# MCU.net
KiCad netlist of a schematic drawn in Altium Designer
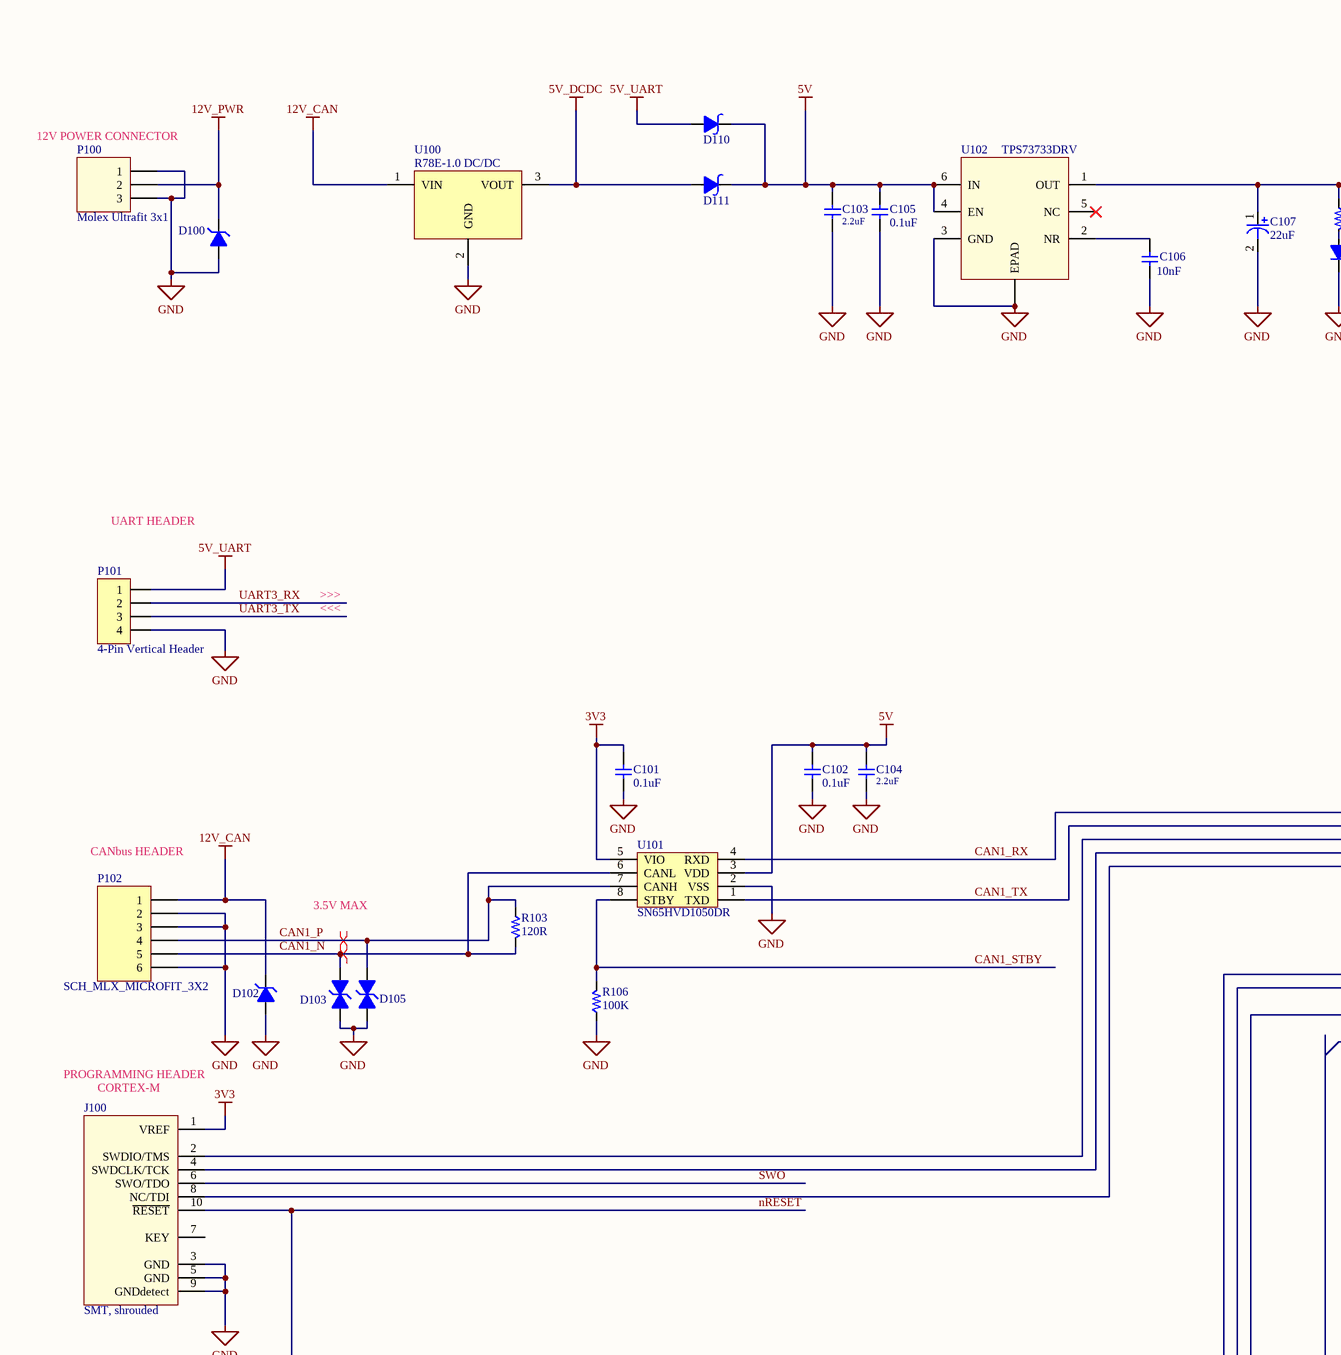
[diagram p0: MCU.SchDoc, top left]
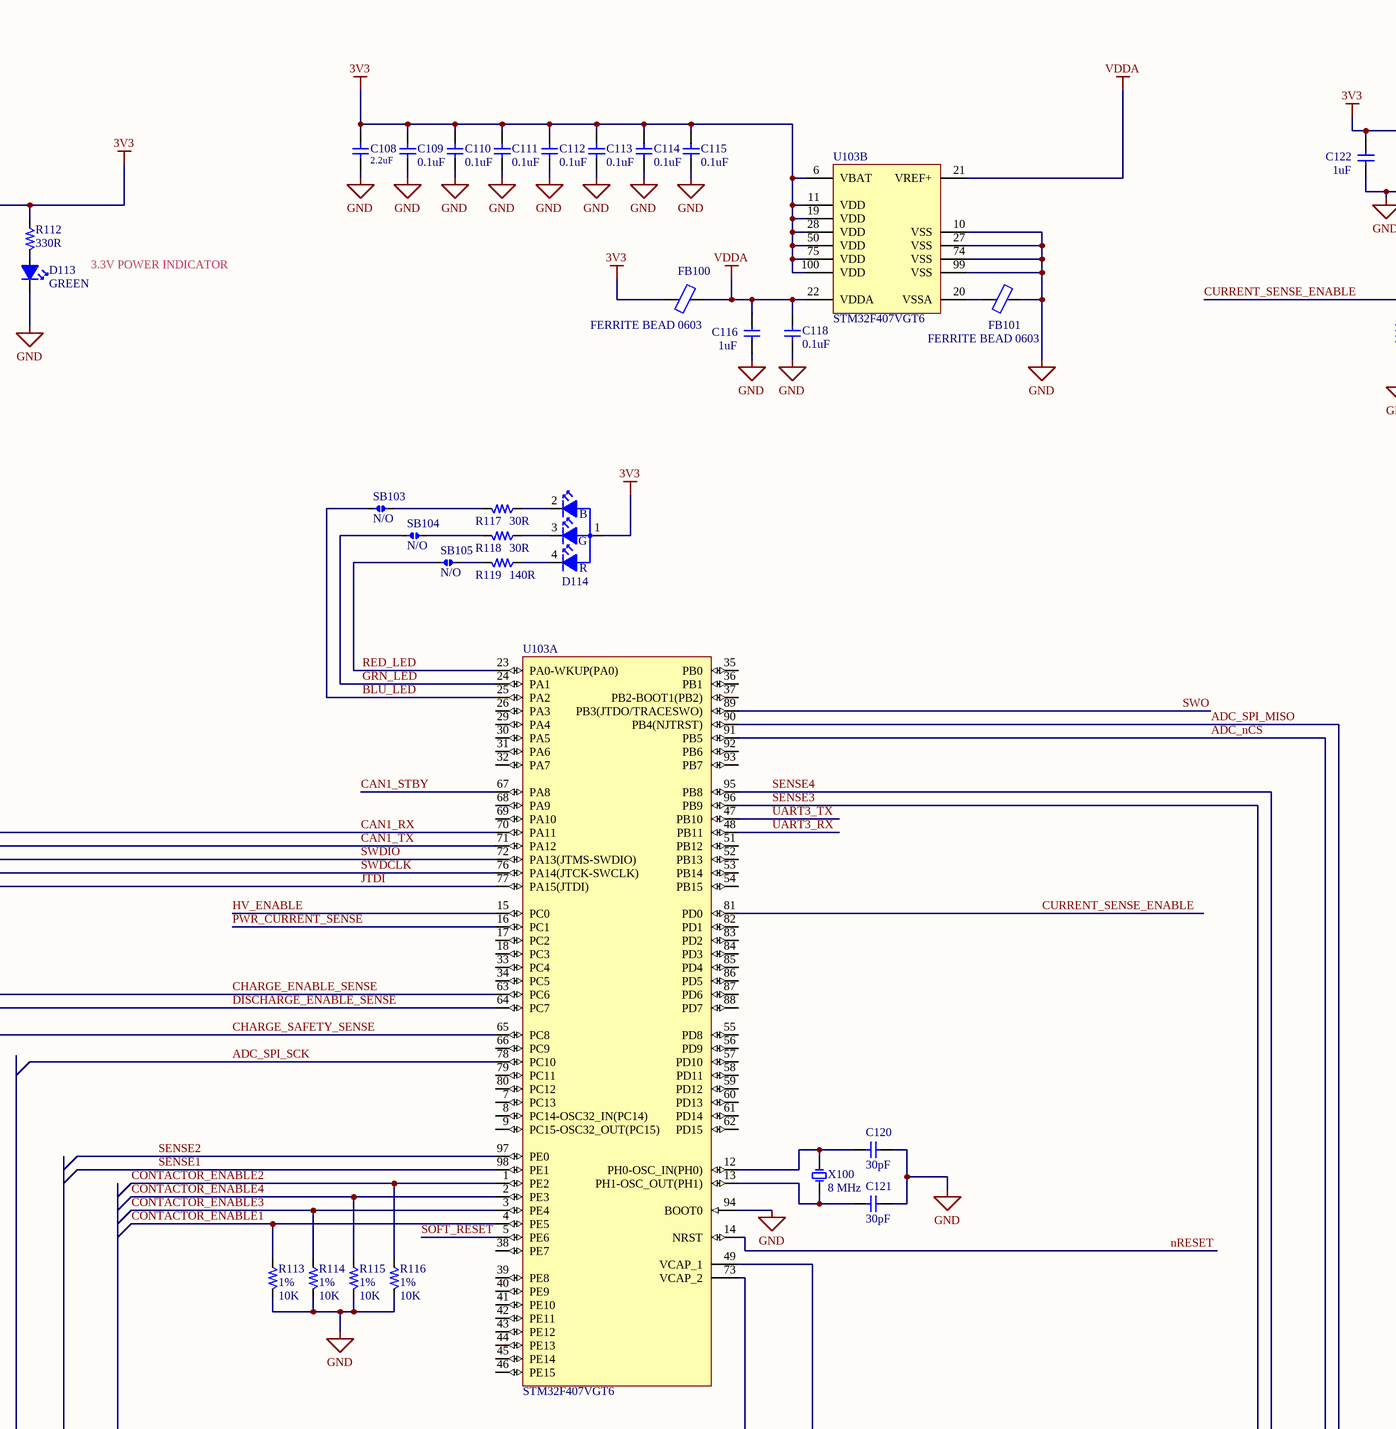
[diagram p1: MCU.SchDoc, top middle]
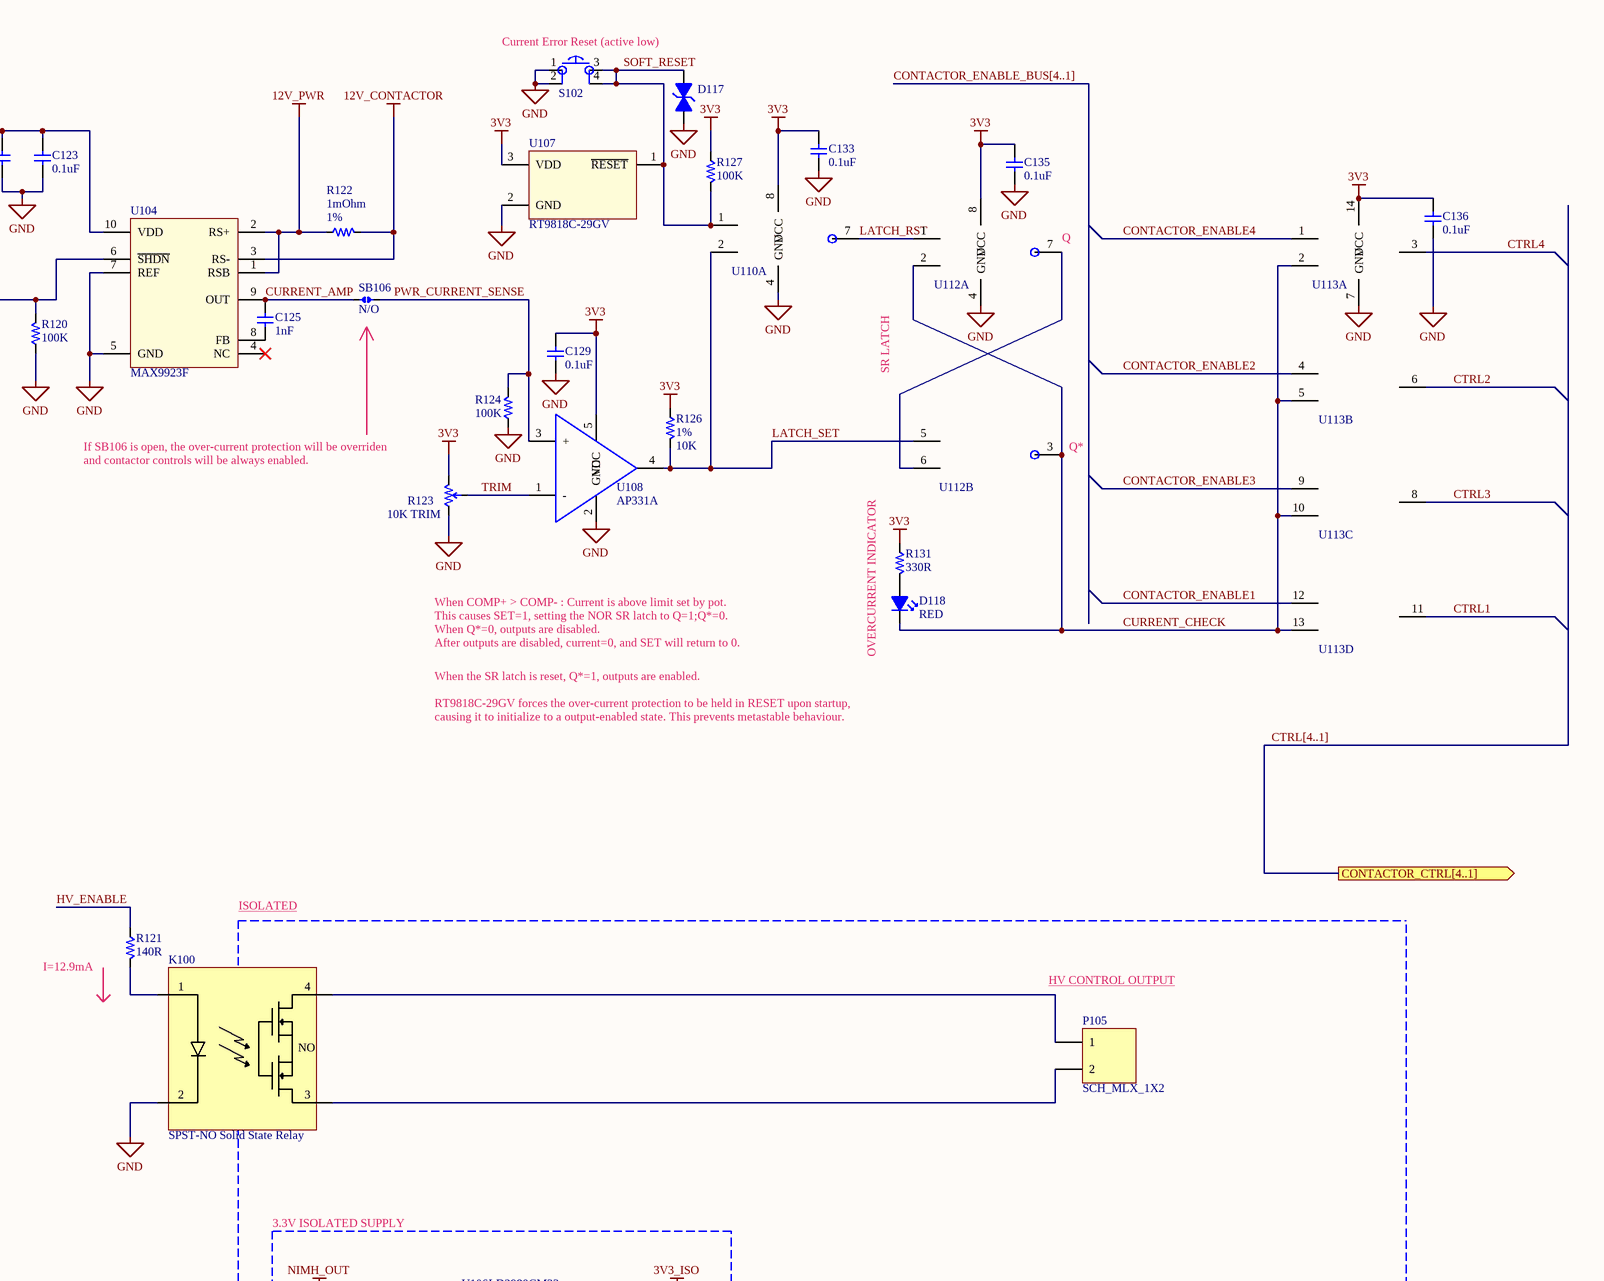
[diagram p2: MCU.SchDoc, top right]
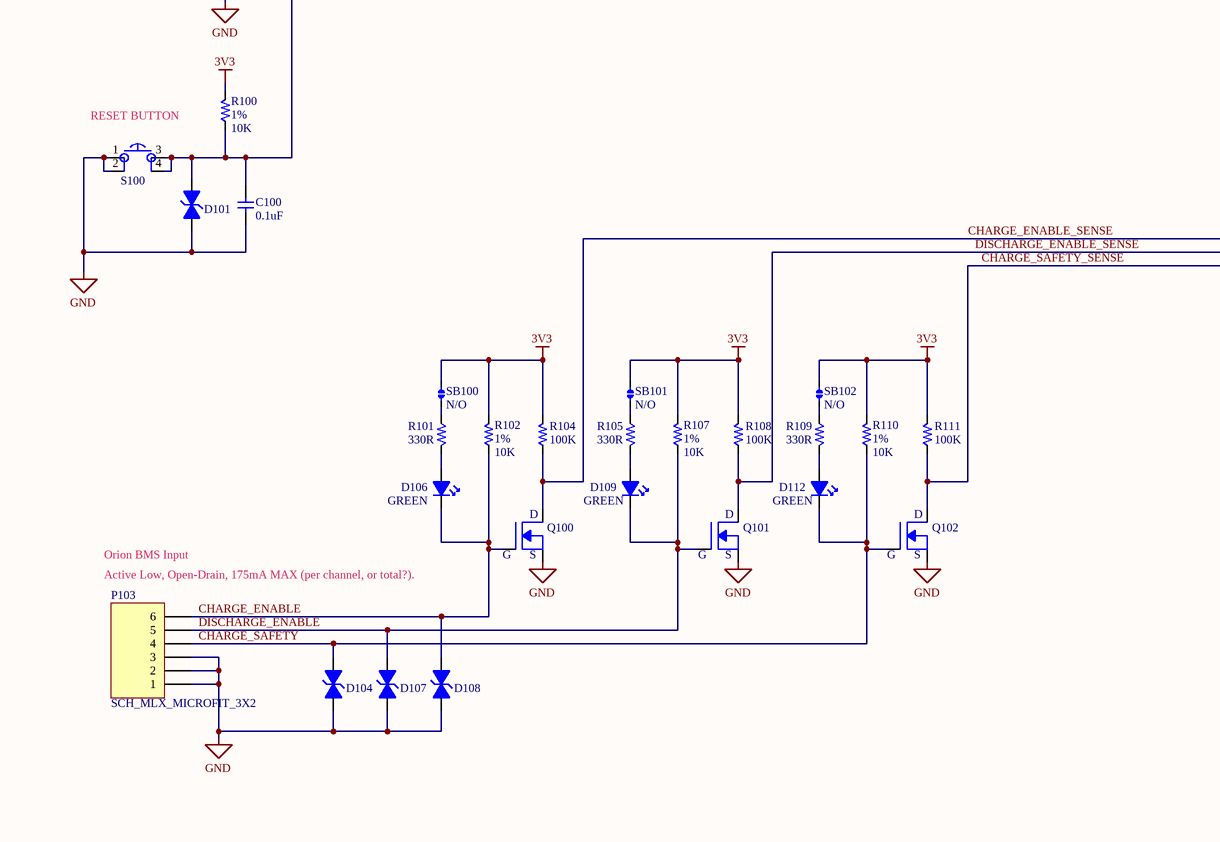
[diagram p3: MCU.SchDoc, bottom left]
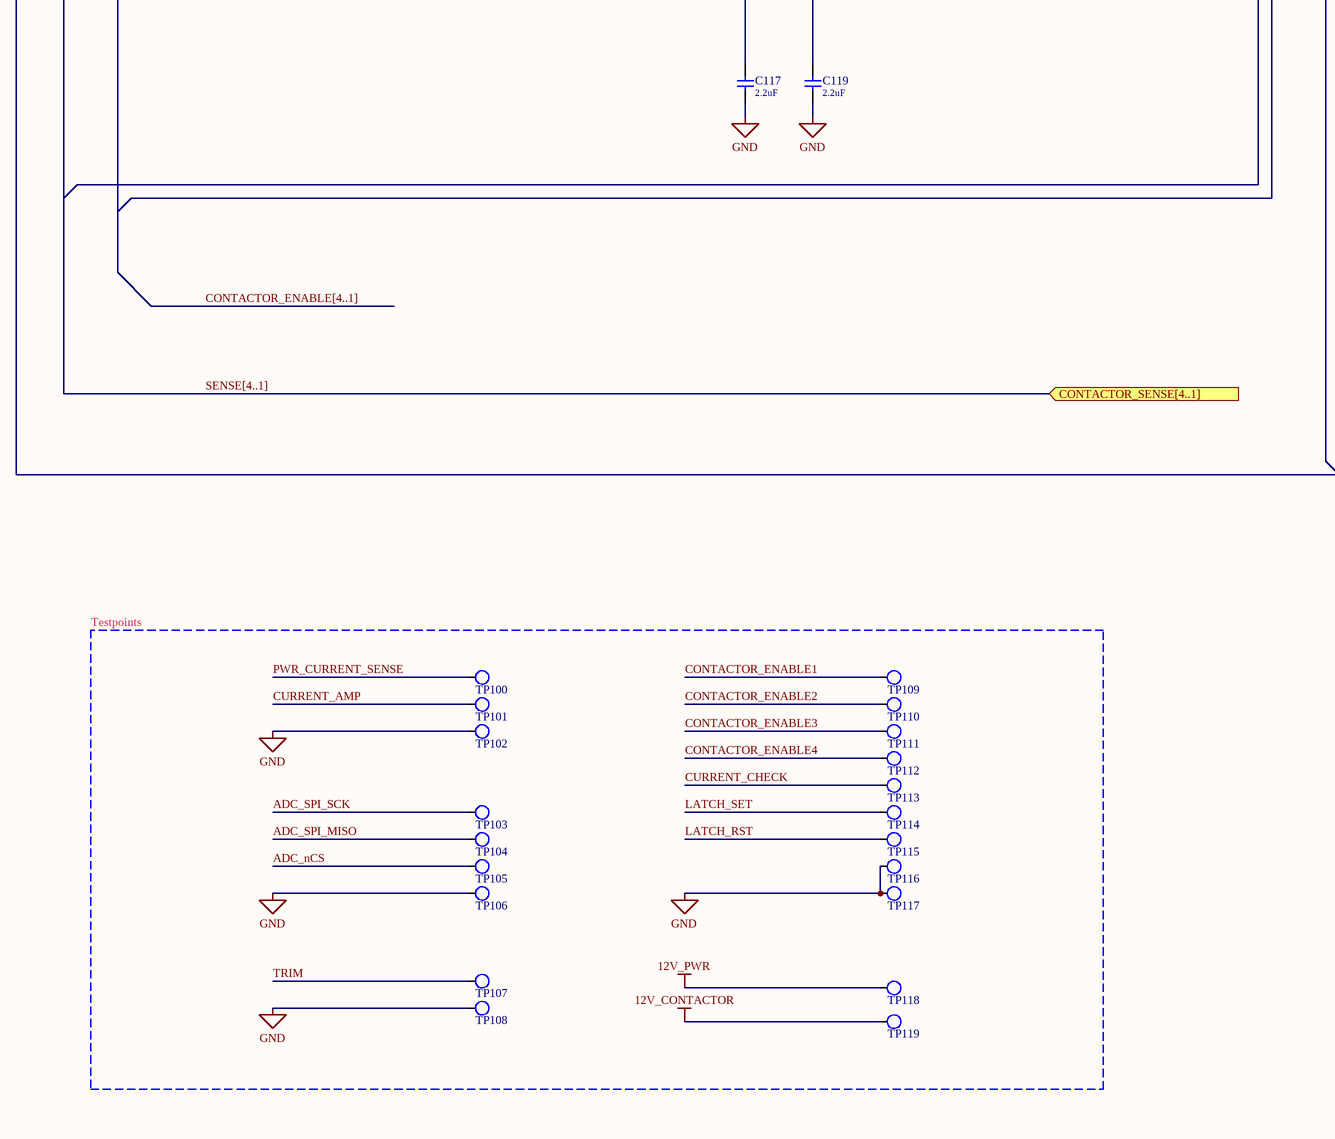
[diagram p4: MCU.SchDoc, bottom middle]
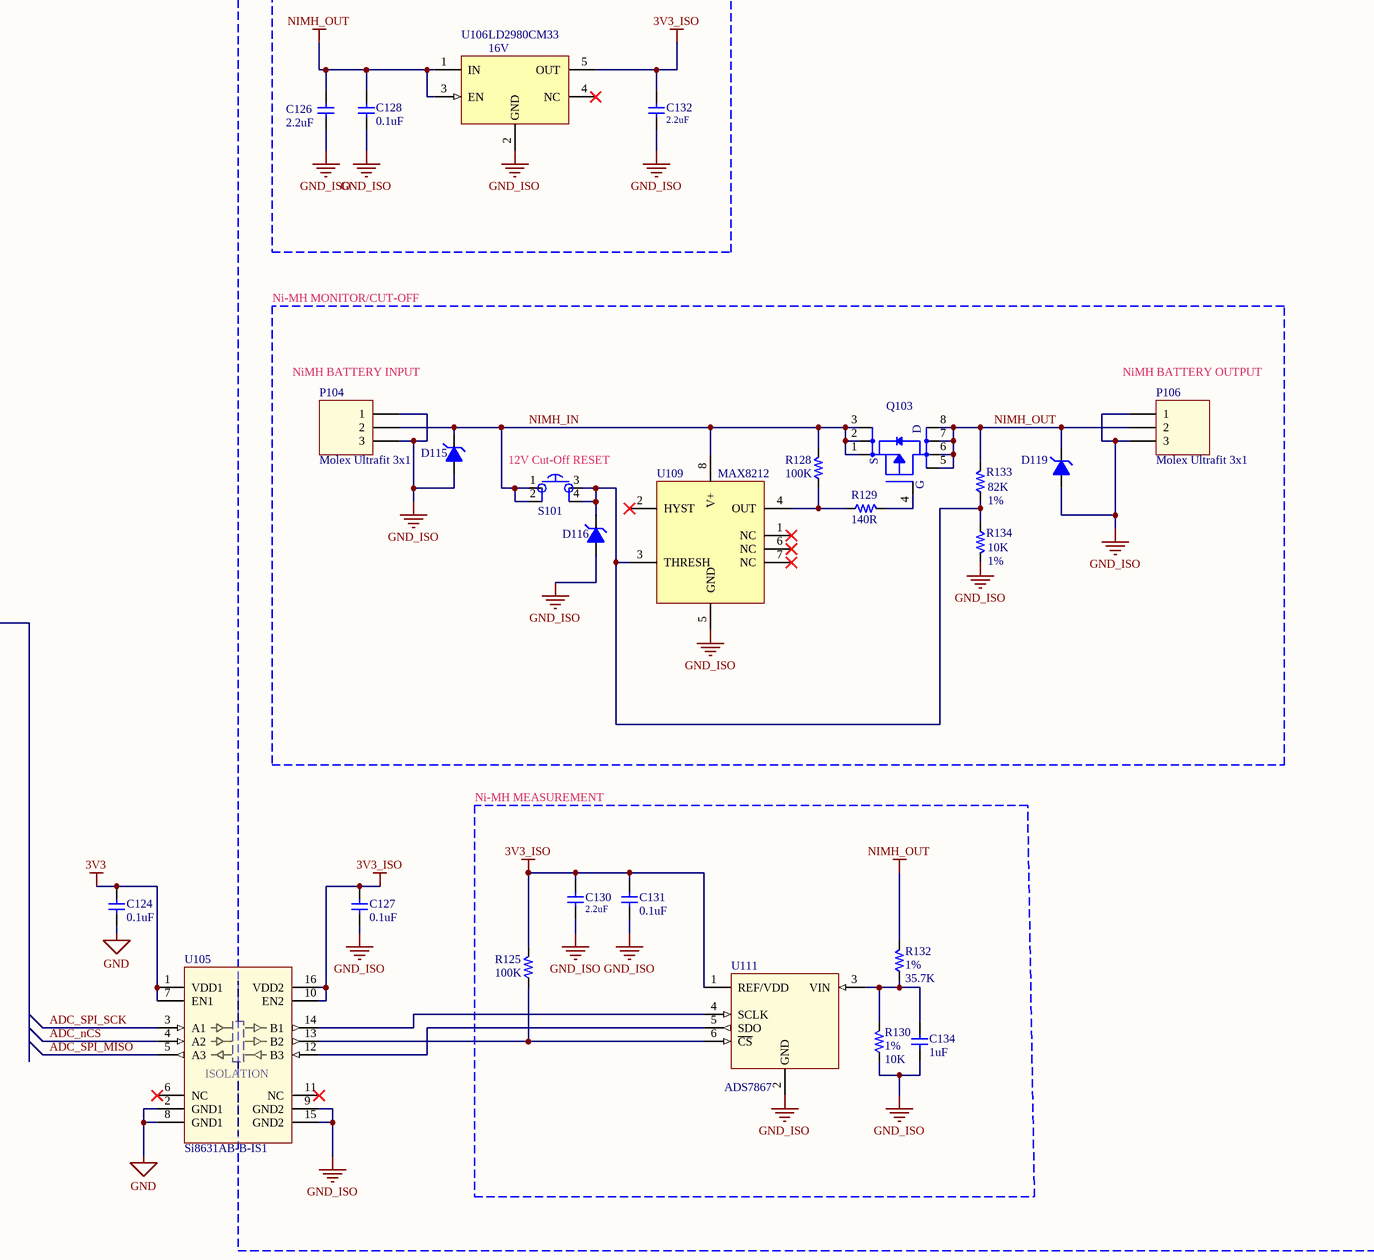
[diagram p5: MCU.SchDoc, bottom right]

(export (version "E")
  (design (tool "Eeschema 10.0.6"))
  (components
    (comp (ref "C100")
      (value "0.1uF")
      (footprint "CAPC1005X06N")
      (description "CAP CER 0402 0.1uF 10V X5R 10%")
      (fields (field (name "TOLERANCE") "10%") (field (name "VOLTAGE") "10V"))
      (libsource (lib "CAP-0402") (part "C040-000U1-00"))
    )
    (comp (ref "C101")
      (value "0.1uF")
      (footprint "CAPC1005X06N")
      (description "CAP CER 0402 0.1uF 10V X5R 10%")
      (fields (field (name "TOLERANCE") "10%") (field (name "VOLTAGE") "10V"))
      (libsource (lib "CAP-0402") (part "C040-000U1-00"))
    )
    (comp (ref "C102")
      (value "0.1uF")
      (footprint "CAPC1005X06N")
      (description "CAP CER 0402 0.1uF 10V X5R 10%")
      (fields (field (name "TOLERANCE") "10%") (field (name "VOLTAGE") "10V"))
      (libsource (lib "CAP-0402") (part "C040-000U1-00"))
    )
    (comp (ref "C103")
      (value "2.2uF")
      (footprint "PCB_GENERIC_SMD_0603")
      (description "CAP CER 0603 2.2uF 16V X5R 20%")
      (fields (field (name "TOLERANCE") "20%") (field (name "VOLTAGE") "16V"))
      (libsource (lib "CAP-0603") (part "C060-002U2-00"))
    )
    (comp (ref "C104")
      (value "2.2uF")
      (footprint "PCB_GENERIC_SMD_0603")
      (description "CAP CER 0603 2.2uF 16V X5R 20%")
      (fields (field (name "TOLERANCE") "20%") (field (name "VOLTAGE") "16V"))
      (libsource (lib "CAP-0603") (part "C060-002U2-00"))
    )
    (comp (ref "C105")
      (value "0.1uF")
      (footprint "CAPC1005X06N")
      (description "CAP CER 0402 0.1uF 10V X5R 10%")
      (fields (field (name "TOLERANCE") "10%") (field (name "VOLTAGE") "10V"))
      (libsource (lib "CAP-0402") (part "C040-000U1-00"))
    )
    (comp (ref "C106")
      (value "10nF")
      (footprint "CAPC1005X06N")
      (description "CAP CER 0402 10nF 50V X7R 10%")
      (fields (field (name "TOLERANCE") "10%") (field (name "VOLTAGE") "50V"))
      (libsource (lib "CAP-0402") (part "C040-0010N-00"))
    )
    (comp (ref "C107")
      (value "22uF")
      (footprint "Tantalum-1206")
      (description "CAP TANT 1206 22uF 6.3V 2.5ohm 20%")
      (fields (field (name "VOLTAGE") "6.3V") (field (name "TOLERANCE") "20%"))
      (libsource (lib "Tantalum-1206") (part "C006-T022U-00"))
    )
    (comp (ref "C108")
      (value "2.2uF")
      (footprint "PCB_GENERIC_SMD_0603")
      (description "CAP CER 0603 2.2uF 16V X5R 20%")
      (fields (field (name "TOLERANCE") "20%") (field (name "VOLTAGE") "16V"))
      (libsource (lib "CAP-0603") (part "C060-002U2-00"))
    )
    (comp (ref "C109")
      (value "0.1uF")
      (footprint "CAPC1005X06N")
      (description "CAP CER 0402 0.1uF 10V X5R 10%")
      (fields (field (name "TOLERANCE") "10%") (field (name "VOLTAGE") "10V"))
      (libsource (lib "CAP-0402") (part "C040-000U1-00"))
    )
    (comp (ref "C110")
      (value "0.1uF")
      (footprint "CAPC1005X06N")
      (description "CAP CER 0402 0.1uF 10V X5R 10%")
      (fields (field (name "TOLERANCE") "10%") (field (name "VOLTAGE") "10V"))
      (libsource (lib "CAP-0402") (part "C040-000U1-00"))
    )
    (comp (ref "C111")
      (value "0.1uF")
      (footprint "CAPC1005X06N")
      (description "CAP CER 0402 0.1uF 10V X5R 10%")
      (fields (field (name "TOLERANCE") "10%") (field (name "VOLTAGE") "10V"))
      (libsource (lib "CAP-0402") (part "C040-000U1-00"))
    )
    (comp (ref "C112")
      (value "0.1uF")
      (footprint "CAPC1005X06N")
      (description "CAP CER 0402 0.1uF 10V X5R 10%")
      (fields (field (name "TOLERANCE") "10%") (field (name "VOLTAGE") "10V"))
      (libsource (lib "CAP-0402") (part "C040-000U1-00"))
    )
    (comp (ref "C113")
      (value "0.1uF")
      (footprint "CAPC1005X06N")
      (description "CAP CER 0402 0.1uF 10V X5R 10%")
      (fields (field (name "TOLERANCE") "10%") (field (name "VOLTAGE") "10V"))
      (libsource (lib "CAP-0402") (part "C040-000U1-00"))
    )
    (comp (ref "C114")
      (value "0.1uF")
      (footprint "CAPC1005X06N")
      (description "CAP CER 0402 0.1uF 10V X5R 10%")
      (fields (field (name "TOLERANCE") "10%") (field (name "VOLTAGE") "10V"))
      (libsource (lib "CAP-0402") (part "C040-000U1-00"))
    )
    (comp (ref "C115")
      (value "0.1uF")
      (footprint "CAPC1005X06N")
      (description "CAP CER 0402 0.1uF 10V X5R 10%")
      (fields (field (name "TOLERANCE") "10%") (field (name "VOLTAGE") "10V"))
      (libsource (lib "CAP-0402") (part "C040-000U1-00"))
    )
    (comp (ref "C116")
      (value "1uF")
      (footprint "PCB_GENERIC_SMD_0603")
      (description "CAP CER 0603 1uF 16V X5R 20%")
      (fields (field (name "TOLERANCE") "20%") (field (name "VOLTAGE") "16V"))
      (libsource (lib "CAP-0603") (part "C060-0001U-00"))
    )
    (comp (ref "C117")
      (value "2.2uF")
      (footprint "PCB_GENERIC_SMD_0603")
      (description "CAP CER 0603 2.2uF 16V X5R 20%")
      (fields (field (name "TOLERANCE") "20%") (field (name "VOLTAGE") "16V"))
      (libsource (lib "CAP-0603") (part "C060-002U2-00"))
    )
    (comp (ref "C118")
      (value "0.1uF")
      (footprint "CAPC1005X06N")
      (description "CAP CER 0402 0.1uF 10V X5R 10%")
      (fields (field (name "TOLERANCE") "10%") (field (name "VOLTAGE") "10V"))
      (libsource (lib "CAP-0402") (part "C040-000U1-00"))
    )
    (comp (ref "C119")
      (value "2.2uF")
      (footprint "PCB_GENERIC_SMD_0603")
      (description "CAP CER 0603 2.2uF 16V X5R 20%")
      (fields (field (name "TOLERANCE") "20%") (field (name "VOLTAGE") "16V"))
      (libsource (lib "CAP-0603") (part "C060-002U2-00"))
    )
    (comp (ref "C120")
      (value "30pF")
      (footprint "CAPC1005X06N")
      (description "CAP CER 0402 30pF 25V NP0 5%")
      (fields (field (name "TOLERANCE") "5%") (field (name "VOLTAGE") "25V"))
      (libsource (lib "CAP-0402") (part "C040-0030P-00"))
    )
    (comp (ref "C121")
      (value "30pF")
      (footprint "CAPC1005X06N")
      (description "CAP CER 0402 30pF 25V NP0 5%")
      (fields (field (name "TOLERANCE") "5%") (field (name "VOLTAGE") "25V"))
      (libsource (lib "CAP-0402") (part "C040-0030P-00"))
    )
    (comp (ref "C122")
      (value "1uF")
      (footprint "PCB_GENERIC_SMD_0603")
      (description "CAP CER 0603 1uF 16V X5R 20%")
      (fields (field (name "TOLERANCE") "20%") (field (name "VOLTAGE") "16V"))
      (libsource (lib "CAP-0603") (part "C060-0001U-00"))
    )
    (comp (ref "C123")
      (value "0.1uF")
      (footprint "CAPC1005X06N")
      (description "CAP CER 0402 0.1uF 10V X5R 10%")
      (fields (field (name "TOLERANCE") "10%") (field (name "VOLTAGE") "10V"))
      (libsource (lib "CAP-0402") (part "C040-000U1-00"))
    )
    (comp (ref "C124")
      (value "0.1uF")
      (footprint "CAPC1005X06N")
      (description "CAP CER 0402 0.1uF 10V X5R 10%")
      (fields (field (name "TOLERANCE") "10%") (field (name "VOLTAGE") "10V"))
      (libsource (lib "CAP-0402") (part "C040-000U1-00"))
    )
    (comp (ref "C125")
      (value "1nF")
      (footprint "CAPC1005X06N")
      (description "CAP CER 0402 1nF 50V X7R 10%")
      (fields (field (name "TOLERANCE") "10%") (field (name "VOLTAGE") "50V"))
      (libsource (lib "CAP-0402") (part "C040-0001N-00"))
    )
    (comp (ref "C126")
      (value "2.2uF")
      (footprint "PCB_GENERIC_SMD_0603")
      (description "CAP CER 0603 2.2uF 16V X5R 20%")
      (fields (field (name "TOLERANCE") "20%") (field (name "VOLTAGE") "16V"))
      (libsource (lib "CAP-0603") (part "C060-002U2-00"))
    )
    (comp (ref "C127")
      (value "0.1uF")
      (footprint "CAPC1005X06N")
      (description "CAP CER 0402 0.1uF 10V X5R 10%")
      (fields (field (name "TOLERANCE") "10%") (field (name "VOLTAGE") "10V"))
      (libsource (lib "CAP-0402") (part "C040-000U1-00"))
    )
    (comp (ref "C128")
      (value "0.1uF")
      (footprint "CAPC1005X06N")
      (description "CAP CER 0402 0.1uF 10V X5R 10%")
      (fields (field (name "TOLERANCE") "10%") (field (name "VOLTAGE") "10V"))
      (libsource (lib "CAP-0402") (part "C040-000U1-00"))
    )
    (comp (ref "C129")
      (value "0.1uF")
      (footprint "CAPC1005X06N")
      (description "CAP CER 0402 0.1uF 10V X5R 10%")
      (fields (field (name "TOLERANCE") "10%") (field (name "VOLTAGE") "10V"))
      (libsource (lib "CAP-0402") (part "C040-000U1-00"))
    )
    (comp (ref "C130")
      (value "2.2uF")
      (footprint "PCB_GENERIC_SMD_0603")
      (description "CAP CER 0603 2.2uF 16V X5R 20%")
      (fields (field (name "TOLERANCE") "20%") (field (name "VOLTAGE") "16V"))
      (libsource (lib "CAP-0603") (part "C060-002U2-00"))
    )
    (comp (ref "C131")
      (value "0.1uF")
      (footprint "CAPC1005X06N")
      (description "CAP CER 0402 0.1uF 10V X5R 10%")
      (fields (field (name "TOLERANCE") "10%") (field (name "VOLTAGE") "10V"))
      (libsource (lib "CAP-0402") (part "C040-000U1-00"))
    )
    (comp (ref "C132")
      (value "2.2uF")
      (footprint "PCB_GENERIC_SMD_0603")
      (description "CAP CER 0603 2.2uF 16V X5R 20%")
      (fields (field (name "TOLERANCE") "20%") (field (name "VOLTAGE") "16V"))
      (libsource (lib "CAP-0603") (part "C060-002U2-00"))
    )
    (comp (ref "C133")
      (value "0.1uF")
      (footprint "CAPC1005X06N")
      (description "CAP CER 0402 0.1uF 10V X5R 10%")
      (fields (field (name "TOLERANCE") "10%") (field (name "VOLTAGE") "10V"))
      (libsource (lib "CAP-0402") (part "C040-000U1-00"))
    )
    (comp (ref "C134")
      (value "1uF")
      (footprint "PCB_GENERIC_SMD_0603")
      (description "CAP CER 0603 1uF 16V X5R 20%")
      (fields (field (name "TOLERANCE") "20%") (field (name "VOLTAGE") "16V"))
      (libsource (lib "CAP-0603") (part "C060-0001U-00"))
    )
    (comp (ref "C135")
      (value "0.1uF")
      (footprint "CAPC1005X06N")
      (description "CAP CER 0402 0.1uF 10V X5R 10%")
      (fields (field (name "TOLERANCE") "10%") (field (name "VOLTAGE") "10V"))
      (libsource (lib "CAP-0402") (part "C040-000U1-00"))
    )
    (comp (ref "C136")
      (value "0.1uF")
      (footprint "CAPC1005X06N")
      (description "CAP CER 0402 0.1uF 10V X5R 10%")
      (fields (field (name "TOLERANCE") "10%") (field (name "VOLTAGE") "10V"))
      (libsource (lib "CAP-0402") (part "C040-000U1-00"))
    )
    (comp (ref "D100")
      (value "TVS_14V_UNI")
      (footprint "SODFL370X108-2N")
      (description "TVS DIODE 14VWM 23.2VC SMF")
      (libsource (lib "TVS Diode Unidirectional 14V") (part "TVS_14V_UNI"))
    )
    (comp (ref "D101")
      (value "Bourns TVS Diode 3.3V SOD323")
      (footprint "TVS Diode SOD-323")
      (description "TVS DIODE 3.3VWM 10.9VC SOD323")
      (libsource (lib "TVS Diode 3V3") (part "Bourns TVS Diode 3.3V SOD323"))
    )
    (comp (ref "D102")
      (value "TVS_14V_UNI")
      (footprint "SODFL370X108-2N")
      (description "TVS DIODE 14VWM 23.2VC SMF")
      (libsource (lib "TVS Diode Unidirectional 14V") (part "TVS_14V_UNI"))
    )
    (comp (ref "D103")
      (value "LittleFuse_SP4021-01FTG-C")
      (footprint "TVS Diode SOD-323")
      (description "TVS DIODE 5VWM 19.6VC BI SOD323")
      (libsource (lib "TVS Diode Bi 5V") (part "LittleFuse_SP4021-01FTG-C"))
    )
    (comp (ref "D104")
      (value "Bourns TVS Diode 3.3V SOD323")
      (footprint "TVS Diode SOD-323")
      (description "TVS DIODE 3.3VWM 10.9VC SOD323")
      (libsource (lib "TVS Diode 3V3") (part "Bourns TVS Diode 3.3V SOD323"))
    )
    (comp (ref "D105")
      (value "LittleFuse_SP4021-01FTG-C")
      (footprint "TVS Diode SOD-323")
      (description "TVS DIODE 5VWM 19.6VC BI SOD323")
      (libsource (lib "TVS Diode Bi 5V") (part "LittleFuse_SP4021-01FTG-C"))
    )
    (comp (ref "D106")
      (value "D060-000G2-00")
      (footprint "SMD_0603_LED")
      (description "LED 0603 GREEN 3.2Vf 20mA")
      (fields (field (name "COLOR") "GREEN"))
      (libsource (lib "LED-0603") (part "D060-000G2-00"))
    )
    (comp (ref "D107")
      (value "Bourns TVS Diode 3.3V SOD323")
      (footprint "TVS Diode SOD-323")
      (description "TVS DIODE 3.3VWM 10.9VC SOD323")
      (libsource (lib "TVS Diode 3V3") (part "Bourns TVS Diode 3.3V SOD323"))
    )
    (comp (ref "D108")
      (value "Bourns TVS Diode 3.3V SOD323")
      (footprint "TVS Diode SOD-323")
      (description "TVS DIODE 3.3VWM 10.9VC SOD323")
      (libsource (lib "TVS Diode 3V3") (part "Bourns TVS Diode 3.3V SOD323"))
    )
    (comp (ref "D109")
      (value "D060-000G2-00")
      (footprint "SMD_0603_LED")
      (description "LED 0603 GREEN 3.2Vf 20mA")
      (fields (field (name "COLOR") "GREEN"))
      (libsource (lib "LED-0603") (part "D060-000G2-00"))
    )
    (comp (ref "D110")
      (value "ONSEMI_MBRM110LT1G")
      (footprint "ON Semi Schottky Diode - MBRM110LT1G")
      (description "DIODE SCHOTTKY 10V 1A")
      (libsource (lib "ON Semi Schottky Diode") (part "ONSEMI_MBRM110LT1G"))
    )
    (comp (ref "D111")
      (value "ONSEMI_MBRM110LT1G")
      (footprint "ON Semi Schottky Diode - MBRM110LT1G")
      (description "DIODE SCHOTTKY 10V 1A")
      (libsource (lib "ON Semi Schottky Diode") (part "ONSEMI_MBRM110LT1G"))
    )
    (comp (ref "D112")
      (value "D060-000G2-00")
      (footprint "SMD_0603_LED")
      (description "LED 0603 GREEN 3.2Vf 20mA")
      (fields (field (name "COLOR") "GREEN"))
      (libsource (lib "LED-0603") (part "D060-000G2-00"))
    )
    (comp (ref "D113")
      (value "D060-000G2-00")
      (footprint "SMD_0603_LED")
      (description "LED 0603 GREEN 3.2Vf 20mA")
      (fields (field (name "COLOR") "GREEN"))
      (libsource (lib "LED-0603") (part "D060-000G2-00"))
    )
    (comp (ref "D114")
      (value "D0S4-000CR-00")
      (footprint "CLMVB-FKA")
      (description "LED 4SMD RGB 2Vf 3Vf 3Vf 20mA 10mA 10mA")
      (libsource (lib "LED-4SMD") (part "D0S4-000CR-00"))
    )
    (comp (ref "D115")
      (value "TVS_14V_UNI")
      (footprint "SODFL370X108-2N")
      (description "TVS DIODE 14VWM 23.2VC SMF")
      (libsource (lib "TVS Diode Unidirectional 14V") (part "TVS_14V_UNI"))
    )
    (comp (ref "D116")
      (value "TVS_14V_UNI")
      (footprint "SODFL370X108-2N")
      (description "TVS DIODE 14VWM 23.2VC SMF")
      (libsource (lib "TVS Diode Unidirectional 14V") (part "TVS_14V_UNI"))
    )
    (comp (ref "D117")
      (value "Bourns TVS Diode 3.3V SOD323")
      (footprint "TVS Diode SOD-323")
      (description "TVS DIODE 3.3VWM 10.9VC SOD323")
      (libsource (lib "TVS Diode 3V3") (part "Bourns TVS Diode 3.3V SOD323"))
    )
    (comp (ref "D118")
      (value "D060-000R2-00")
      (footprint "SMD_0603_LED")
      (description "LED 0603 RED 2Vf 20mA")
      (fields (field (name "COLOR") "RED"))
      (libsource (lib "LED-0603") (part "D060-000R2-00"))
    )
    (comp (ref "D119")
      (value "TVS_14V_UNI")
      (footprint "SODFL370X108-2N")
      (description "TVS DIODE 14VWM 23.2VC SMF")
      (libsource (lib "TVS Diode Unidirectional 14V") (part "TVS_14V_UNI"))
    )
    (comp (ref "FB100")
      (value "FERRITE BEAD 0603")
      (footprint "INDC1608X10N")
      (description "Ferrite Bead, 0603, 600Ohm @ 100MHz, 200mOhm DC")
      (libsource (lib "0603-FERRITE-600Ohm") (part "0603_FERRITE_600Ohm"))
    )
    (comp (ref "FB101")
      (value "FERRITE BEAD 0603")
      (footprint "INDC1608X10N")
      (description "Ferrite Bead, 0603, 600Ohm @ 100MHz, 200mOhm DC")
      (libsource (lib "0603-FERRITE-600Ohm") (part "0603_FERRITE_600Ohm"))
    )
    (comp (ref "J100")
      (value "SMT, shrouded")
      (footprint "CONN-50mil-10POS-SMD")
      (description "ARM Cortex-M 10pin connector,shrouded,SMT")
      (libsource (lib "CONN-50mil-cortexM") (part "conn_0.050{dblquote}_cortexM"))
    )
    (comp (ref "K100")
      (value "SPST-NO Solid State Relay")
      (footprint "SPST-NO Solid State Relay - IXYS")
      (libsource (lib "SPST-NO Solid State Relay") (part "SPST-NO Solid State Relay"))
    )
    (comp (ref "P100")
      (value "Molex Ultrafit 3x1")
      (footprint "Molex-Ultrafit-3x1")
      (description "Molex Ultrafit 3x1 - 172310-1303")
      (libsource (lib "Molex Ultrafit 3x1 - 172310-1303") (part "Molex-Ultrafit-3x1"))
    )
    (comp (ref "P101")
      (value "4-Pin Vertical Header")
      (footprint "4-Pin Vertical Header")
      (fields (field (name "MANUFACTURER") "Sullins"))
      (libsource (lib "4 Pin 100 mil Vertical Header - Through Hole") (part "4-Pin Vertical Header"))
    )
    (comp (ref "P102")
      (value "SCH_MLX_MICROFIT_3X2")
      (footprint "PCB_MLX_MICROFIT_3X2")
      (libsource (lib "Molex Microfit 3.0 3x2") (part "SCH_MLX_MICROFIT_3X2"))
    )
    (comp (ref "P103")
      (value "SCH_MLX_MICROFIT_3X2")
      (footprint "PCB_MLX_MICROFIT_3X2")
      (libsource (lib "") (part "SCH_MLX_MICROFIT_3X2_1"))
    )
    (comp (ref "P104")
      (value "Molex Ultrafit 3x1")
      (footprint "Molex-Ultrafit-3x1")
      (description "Molex Ultrafit 3x1 - 172310-1303")
      (libsource (lib "Molex Ultrafit 3x1 - 172310-1303") (part "Molex-Ultrafit-3x1"))
    )
    (comp (ref "P105")
      (value "SCH_MLX_1X2")
      (footprint "PCB_MLX_MICROFIT_1X2")
      (libsource (lib "Molex Microfit 3.0 1x2") (part "SCH_MLX_1X2"))
    )
    (comp (ref "P106")
      (value "Molex Ultrafit 3x1")
      (footprint "Molex-Ultrafit-3x1")
      (description "Molex Ultrafit 3x1 - 172310-1303")
      (libsource (lib "") (part "Molex-Ultrafit-3x1_1"))
    )
    (comp (ref "Q100")
      (value "NMOS - SSM3K333R")
      (footprint "NMOS - SSM3K333R - SOTFL95P180X88-3M")
      (description "MOSFET N CH 30V 6A 2-3Z1A")
      (libsource (lib "Toshiba NMOS - SOT23-F") (part "NMOS - SSM3K333R"))
    )
    (comp (ref "Q101")
      (value "NMOS - SSM3K333R")
      (footprint "NMOS - SSM3K333R - SOTFL95P180X88-3M")
      (description "MOSFET N CH 30V 6A 2-3Z1A")
      (libsource (lib "Toshiba NMOS - SOT23-F") (part "NMOS - SSM3K333R"))
    )
    (comp (ref "Q102")
      (value "NMOS - SSM3K333R")
      (footprint "NMOS - SSM3K333R - SOTFL95P180X88-3M")
      (description "MOSFET N CH 30V 6A 2-3Z1A")
      (libsource (lib "Toshiba NMOS - SOT23-F") (part "NMOS - SSM3K333R"))
    )
    (comp (ref "Q103")
      (value "INFINEON BSC030P03NS3 G")
      (footprint "BSC030P03NS3 G")
      (description "P-Channel 30V 25.4A (Ta), 100A (Tc) 2.5W (Ta), 125W (Tc) Surface Mount PG-TDSON-8")
      (libsource (lib "Infineon BSC030P03NS3 G - 8-PowerTDFN - PMOS") (part "BSC030P03NS3 G"))
    )
    (comp (ref "R100")
      (value "10K")
      (footprint "PCB_GENERIC_SMD_0603")
      (description "RES 0603 10K 1% 100mW")
      (fields
        (field (name "TOLERANCE") "1%")
        (field (name "POWER") "100mW")
        (field (name "Comment") "R060-00103-01")
      )
      (libsource (lib "RES-0603") (part "R060-00103-01"))
    )
    (comp (ref "R101")
      (value "330R")
      (footprint "PCB_GENERIC_SMD_0603")
      (description "RES 0603 330ohm 5% 63mW")
      (fields (field (name "TOLERANCE") "5%") (field (name "POWER") "63mW"))
      (libsource (lib "RES-0603") (part "R060-00331-05"))
    )
    (comp (ref "R102")
      (value "10K")
      (footprint "PCB_GENERIC_SMD_0603")
      (description "RES 0603 10K 1% 100mW")
      (fields
        (field (name "TOLERANCE") "1%")
        (field (name "POWER") "100mW")
        (field (name "Comment") "R060-00103-01")
      )
      (libsource (lib "RES-0603") (part "R060-00103-01"))
    )
    (comp (ref "R103")
      (value "120R")
      (footprint "PCB_GENERIC_SMD_0603")
      (description "RES 0603 120ohm 5% 63mW")
      (fields (field (name "TOLERANCE") "5%") (field (name "POWER") "63mW"))
      (libsource (lib "RES-0603") (part "R060-00121-05"))
    )
    (comp (ref "R104")
      (value "100K")
      (footprint "PCB_GENERIC_SMD_0603")
      (description "RES 0603 100K 5% 63mW")
      (fields (field (name "TOLERANCE") "5%") (field (name "POWER") "63mW"))
      (libsource (lib "RES-0603") (part "R060-00104-05"))
    )
    (comp (ref "R105")
      (value "330R")
      (footprint "PCB_GENERIC_SMD_0603")
      (description "RES 0603 330ohm 5% 63mW")
      (fields (field (name "TOLERANCE") "5%") (field (name "POWER") "63mW"))
      (libsource (lib "RES-0603") (part "R060-00331-05"))
    )
    (comp (ref "R106")
      (value "100K")
      (footprint "PCB_GENERIC_SMD_0603")
      (description "RES 0603 100K 5% 63mW")
      (fields (field (name "TOLERANCE") "5%") (field (name "POWER") "63mW"))
      (libsource (lib "RES-0603") (part "R060-00104-05"))
    )
    (comp (ref "R107")
      (value "10K")
      (footprint "PCB_GENERIC_SMD_0603")
      (description "RES 0603 10K 1% 100mW")
      (fields
        (field (name "TOLERANCE") "1%")
        (field (name "POWER") "100mW")
        (field (name "Comment") "R060-00103-01")
      )
      (libsource (lib "RES-0603") (part "R060-00103-01"))
    )
    (comp (ref "R108")
      (value "100K")
      (footprint "PCB_GENERIC_SMD_0603")
      (description "RES 0603 100K 5% 63mW")
      (fields (field (name "TOLERANCE") "5%") (field (name "POWER") "63mW"))
      (libsource (lib "RES-0603") (part "R060-00104-05"))
    )
    (comp (ref "R109")
      (value "330R")
      (footprint "PCB_GENERIC_SMD_0603")
      (description "RES 0603 330ohm 5% 63mW")
      (fields (field (name "TOLERANCE") "5%") (field (name "POWER") "63mW"))
      (libsource (lib "RES-0603") (part "R060-00331-05"))
    )
    (comp (ref "R110")
      (value "10K")
      (footprint "PCB_GENERIC_SMD_0603")
      (description "RES 0603 10K 1% 100mW")
      (fields
        (field (name "TOLERANCE") "1%")
        (field (name "POWER") "100mW")
        (field (name "Comment") "R060-00103-01")
      )
      (libsource (lib "RES-0603") (part "R060-00103-01"))
    )
    (comp (ref "R111")
      (value "100K")
      (footprint "PCB_GENERIC_SMD_0603")
      (description "RES 0603 100K 5% 63mW")
      (fields (field (name "TOLERANCE") "5%") (field (name "POWER") "63mW"))
      (libsource (lib "RES-0603") (part "R060-00104-05"))
    )
    (comp (ref "R112")
      (value "330R")
      (footprint "PCB_GENERIC_SMD_0603")
      (description "RES 0603 330ohm 5% 63mW")
      (fields (field (name "TOLERANCE") "5%") (field (name "POWER") "63mW"))
      (libsource (lib "RES-0603") (part "R060-00331-05"))
    )
    (comp (ref "R113")
      (value "10K")
      (footprint "PCB_GENERIC_SMD_0603")
      (description "RES 0603 10K 1% 100mW")
      (fields
        (field (name "TOLERANCE") "1%")
        (field (name "POWER") "100mW")
        (field (name "Comment") "R060-00103-01")
      )
      (libsource (lib "RES-0603") (part "R060-00103-01"))
    )
    (comp (ref "R114")
      (value "10K")
      (footprint "PCB_GENERIC_SMD_0603")
      (description "RES 0603 10K 1% 100mW")
      (fields
        (field (name "TOLERANCE") "1%")
        (field (name "POWER") "100mW")
        (field (name "Comment") "R060-00103-01")
      )
      (libsource (lib "RES-0603") (part "R060-00103-01"))
    )
    (comp (ref "R115")
      (value "10K")
      (footprint "PCB_GENERIC_SMD_0603")
      (description "RES 0603 10K 1% 100mW")
      (fields
        (field (name "TOLERANCE") "1%")
        (field (name "POWER") "100mW")
        (field (name "Comment") "R060-00103-01")
      )
      (libsource (lib "RES-0603") (part "R060-00103-01"))
    )
    (comp (ref "R116")
      (value "10K")
      (footprint "PCB_GENERIC_SMD_0603")
      (description "RES 0603 10K 1% 100mW")
      (fields
        (field (name "TOLERANCE") "1%")
        (field (name "POWER") "100mW")
        (field (name "Comment") "R060-00103-01")
      )
      (libsource (lib "RES-0603") (part "R060-00103-01"))
    )
    (comp (ref "R117")
      (value "30R")
      (footprint "PCB_GENERIC_SMD_0603")
      (description "RES 0603 30ohm 5% 100mW")
      (fields (field (name "TOLERANCE") "5%") (field (name "POWER") "100mW"))
      (libsource (lib "RES-0603") (part "R060-00300-05"))
    )
    (comp (ref "R118")
      (value "30R")
      (footprint "PCB_GENERIC_SMD_0603")
      (description "RES 0603 30ohm 5% 100mW")
      (fields (field (name "TOLERANCE") "5%") (field (name "POWER") "100mW"))
      (libsource (lib "RES-0603") (part "R060-00300-05"))
    )
    (comp (ref "R119")
      (value "140R")
      (footprint "PCB_GENERIC_SMD_0603")
      (description "RES 0603 140ohm 5% 63mW")
      (fields (field (name "TOLERANCE") "5%") (field (name "POWER") "63mW"))
      (libsource (lib "RES-0603") (part "R060-00141-05"))
    )
    (comp (ref "R120")
      (value "100K")
      (footprint "PCB_GENERIC_SMD_0603")
      (description "RES 0603 100K 5% 63mW")
      (fields (field (name "TOLERANCE") "5%") (field (name "POWER") "63mW"))
      (libsource (lib "RES-0603") (part "R060-00104-05"))
    )
    (comp (ref "R121")
      (value "140R")
      (footprint "PCB_GENERIC_SMD_0603")
      (description "RES 0603 140ohm 5% 63mW")
      (fields (field (name "TOLERANCE") "5%") (field (name "POWER") "63mW"))
      (libsource (lib "RES-0603") (part "R060-00141-05"))
    )
    (comp (ref "R122")
      (value "resistor_sense_1mOhm_2512")
      (footprint "RESC6432X11N")
      (description "1mOhm Current Sense")
      (fields (field (name "RESISTANCE") "1mOhm") (field (name "TOLERANCE") "1%"))
      (libsource (lib "resistor_sense_1mOhm_2512") (part "resistor_sense_1mOhm_2512"))
    )
    (comp (ref "R123")
      (value "10K TRIM")
      (footprint "10K_TRIM_SMD")
      (description "TRIMMER 10K OHM 0.25W SMD")
      (libsource (lib "COPAL_trimmer_10k_smd") (part "10K_TRIM_SMD"))
    )
    (comp (ref "R124")
      (value "100K")
      (footprint "PCB_GENERIC_SMD_0603")
      (description "RES 0603 100K 5% 63mW")
      (fields (field (name "TOLERANCE") "5%") (field (name "POWER") "63mW"))
      (libsource (lib "RES-0603") (part "R060-00104-05"))
    )
    (comp (ref "R125")
      (value "100K")
      (footprint "PCB_GENERIC_SMD_0603")
      (description "RES 0603 100K 5% 63mW")
      (fields (field (name "TOLERANCE") "5%") (field (name "POWER") "63mW"))
      (libsource (lib "RES-0603") (part "R060-00104-05"))
    )
    (comp (ref "R126")
      (value "10K")
      (footprint "PCB_GENERIC_SMD_0603")
      (description "RES 0603 10K 1% 100mW")
      (fields
        (field (name "TOLERANCE") "1%")
        (field (name "POWER") "100mW")
        (field (name "Comment") "R060-00103-01")
      )
      (libsource (lib "RES-0603") (part "R060-00103-01"))
    )
    (comp (ref "R127")
      (value "100K")
      (footprint "PCB_GENERIC_SMD_0603")
      (description "RES 0603 100K 5% 63mW")
      (fields (field (name "TOLERANCE") "5%") (field (name "POWER") "63mW"))
      (libsource (lib "RES-0603") (part "R060-00104-05"))
    )
    (comp (ref "R128")
      (value "100K")
      (footprint "PCB_GENERIC_SMD_0603")
      (description "RES 0603 100K 5% 63mW")
      (fields (field (name "TOLERANCE") "5%") (field (name "POWER") "63mW"))
      (libsource (lib "RES-0603") (part "R060-00104-05"))
    )
    (comp (ref "R129")
      (value "140R")
      (footprint "PCB_GENERIC_SMD_0603")
      (description "RES 0603 140ohm 5% 63mW")
      (fields (field (name "TOLERANCE") "5%") (field (name "POWER") "63mW"))
      (libsource (lib "RES-0603") (part "R060-00141-05"))
    )
    (comp (ref "R130")
      (value "10K")
      (footprint "PCB_GENERIC_SMD_0603")
      (description "RES 0603 10K 1% 100mW")
      (fields
        (field (name "TOLERANCE") "1%")
        (field (name "POWER") "100mW")
        (field (name "Comment") "R060-00103-01")
      )
      (libsource (lib "RES-0603") (part "R060-00103-01"))
    )
    (comp (ref "R131")
      (value "330R")
      (footprint "PCB_GENERIC_SMD_0603")
      (description "RES 0603 330ohm 5% 63mW")
      (fields (field (name "TOLERANCE") "5%") (field (name "POWER") "63mW"))
      (libsource (lib "RES-0603") (part "R060-00331-05"))
    )
    (comp (ref "R132")
      (value "35.7K")
      (footprint "PCB_GENERIC_SMD_0603")
      (description "RES 0603 35.7K 1% 100mW")
      (fields
        (field (name "TOLERANCE") "1%")
        (field (name "POWER") "100mW")
        (field (name "Comment") "R060-03572-01")
      )
      (libsource (lib "RES-0603") (part "R060-03572-01"))
    )
    (comp (ref "R133")
      (value "82K")
      (footprint "PCB_GENERIC_SMD_0603")
      (description "RES 0603 82K 1% 100mW")
      (fields
        (field (name "TOLERANCE") "1%")
        (field (name "POWER") "100mW")
        (field (name "Comment") "R060-00823-01")
      )
      (libsource (lib "RES-0603") (part "R060-00823-01"))
    )
    (comp (ref "R134")
      (value "10K")
      (footprint "PCB_GENERIC_SMD_0603")
      (description "RES 0603 10K 1% 100mW")
      (fields
        (field (name "TOLERANCE") "1%")
        (field (name "POWER") "100mW")
        (field (name "Comment") "R060-00103-01")
      )
      (libsource (lib "RES-0603") (part "R060-00103-01"))
    )
    (comp (ref "S100")
      (value "Tactile Switch")
      (footprint "C&K 4 pin Tactile Switch")
      (libsource (lib "C&K 4 Pin Tactile Switch") (part "C&K Tactile Switch"))
    )
    (comp (ref "S101")
      (value "Tactile Switch")
      (footprint "C&K 4 pin Tactile Switch")
      (libsource (lib "C&K 4 Pin Tactile Switch") (part "C&K Tactile Switch"))
    )
    (comp (ref "S102")
      (value "Tactile Switch")
      (footprint "C&K 4 pin Tactile Switch")
      (libsource (lib "C&K 4 Pin Tactile Switch") (part "C&K Tactile Switch"))
    )
    (comp (ref "SB100")
      (value "N/O")
      (footprint "SB_ARROW_NC")
      (description "Solder Bridge, Normally Open")
      (libsource (lib "SolderJumper20mil") (part "SB_NO"))
    )
    (comp (ref "SB101")
      (value "N/O")
      (footprint "SB_ARROW_NC")
      (description "Solder Bridge, Normally Open")
      (libsource (lib "SolderJumper20mil") (part "SB_NO"))
    )
    (comp (ref "SB102")
      (value "N/O")
      (footprint "SB_ARROW_NC")
      (description "Solder Bridge, Normally Open")
      (libsource (lib "SolderJumper20mil") (part "SB_NO"))
    )
    (comp (ref "SB103")
      (value "N/O")
      (footprint "SB_ARROW_NC")
      (description "Solder Bridge, Normally Open")
      (libsource (lib "SolderJumper20mil") (part "SB_NO"))
    )
    (comp (ref "SB104")
      (value "N/O")
      (footprint "SB_ARROW_NC")
      (description "Solder Bridge, Normally Open")
      (libsource (lib "SolderJumper20mil") (part "SB_NO"))
    )
    (comp (ref "SB105")
      (value "N/O")
      (footprint "SB_ARROW_NC")
      (description "Solder Bridge, Normally Open")
      (libsource (lib "SolderJumper20mil") (part "SB_NO"))
    )
    (comp (ref "SB106")
      (value "N/O")
      (footprint "SB_ARROW_NC")
      (description "Solder Bridge, Normally Open")
      (libsource (lib "SolderJumper20mil") (part "SB_NO"))
    )
    (comp (ref "TP100")
      (value "TESTPOINT")
      (footprint "TP08")
      (description "Testpoint")
      (libsource (lib "MftrFeature") (part "TESTPOINT"))
    )
    (comp (ref "TP101")
      (value "TESTPOINT")
      (footprint "TP08")
      (description "Testpoint")
      (libsource (lib "MftrFeature") (part "TESTPOINT"))
    )
    (comp (ref "TP102")
      (value "TESTPOINT")
      (footprint "TP08")
      (description "Testpoint")
      (libsource (lib "MftrFeature") (part "TESTPOINT"))
    )
    (comp (ref "TP103")
      (value "TESTPOINT")
      (footprint "TP08")
      (description "Testpoint")
      (libsource (lib "MftrFeature") (part "TESTPOINT"))
    )
    (comp (ref "TP104")
      (value "TESTPOINT")
      (footprint "TP08")
      (description "Testpoint")
      (libsource (lib "MftrFeature") (part "TESTPOINT"))
    )
    (comp (ref "TP105")
      (value "TESTPOINT")
      (footprint "TP08")
      (description "Testpoint")
      (libsource (lib "MftrFeature") (part "TESTPOINT"))
    )
    (comp (ref "TP106")
      (value "TESTPOINT")
      (footprint "TP08")
      (description "Testpoint")
      (libsource (lib "MftrFeature") (part "TESTPOINT"))
    )
    (comp (ref "TP107")
      (value "TESTPOINT")
      (footprint "TP08")
      (description "Testpoint")
      (libsource (lib "MftrFeature") (part "TESTPOINT"))
    )
    (comp (ref "TP108")
      (value "TESTPOINT")
      (footprint "TP08")
      (description "Testpoint")
      (libsource (lib "MftrFeature") (part "TESTPOINT"))
    )
    (comp (ref "TP109")
      (value "TESTPOINT")
      (footprint "TP08")
      (description "Testpoint")
      (libsource (lib "MftrFeature") (part "TESTPOINT"))
    )
    (comp (ref "TP110")
      (value "TESTPOINT")
      (footprint "TP08")
      (description "Testpoint")
      (libsource (lib "MftrFeature") (part "TESTPOINT"))
    )
    (comp (ref "TP111")
      (value "TESTPOINT")
      (footprint "TP08")
      (description "Testpoint")
      (libsource (lib "MftrFeature") (part "TESTPOINT"))
    )
    (comp (ref "TP112")
      (value "TESTPOINT")
      (footprint "TP08")
      (description "Testpoint")
      (libsource (lib "MftrFeature") (part "TESTPOINT"))
    )
    (comp (ref "TP113")
      (value "TESTPOINT")
      (footprint "TP08")
      (description "Testpoint")
      (libsource (lib "MftrFeature") (part "TESTPOINT"))
    )
    (comp (ref "TP114")
      (value "TESTPOINT")
      (footprint "TP08")
      (description "Testpoint")
      (libsource (lib "MftrFeature") (part "TESTPOINT"))
    )
    (comp (ref "TP115")
      (value "TESTPOINT")
      (footprint "TP08")
      (description "Testpoint")
      (libsource (lib "MftrFeature") (part "TESTPOINT"))
    )
    (comp (ref "TP116")
      (value "TESTPOINT")
      (footprint "TP08")
      (description "Testpoint")
      (libsource (lib "MftrFeature") (part "TESTPOINT"))
    )
    (comp (ref "TP117")
      (value "TESTPOINT")
      (footprint "TP08")
      (description "Testpoint")
      (libsource (lib "MftrFeature") (part "TESTPOINT"))
    )
    (comp (ref "TP118")
      (value "TESTPOINT")
      (footprint "TP08")
      (description "Testpoint")
      (libsource (lib "MftrFeature") (part "TESTPOINT"))
    )
    (comp (ref "TP119")
      (value "TESTPOINT")
      (footprint "TP08")
      (description "Testpoint")
      (libsource (lib "MftrFeature") (part "TESTPOINT"))
    )
    (comp (ref "U100")
      (value "R78E-1.0 DC/DC")
      (footprint "R78-1.0")
      (libsource (lib "Recom R78E-1.0") (part "R78E-1.0"))
    )
    (comp (ref "U101")
      (value "SN65HVD1050DR")
      (footprint "SOIC127P600X175-8N")
      (description "IC EMC CAN TRANSCEIVER 8-SOIC")
      (libsource (lib "TI_SN65HVD1050DR") (part "SN65HVD1050DR"))
    )
    (comp (ref "U102")
      (value "TPS73733DRV")
      (footprint "SON65P200X80_HS-7M")
      (description "IC REG LDO 3.3V 1A 6SON")
      (libsource (lib "3V3LDO_TPS73733DRV") (part "TPS73733DRV"))
    )
    (comp (ref "U103")
      (value "STM32F407VGT6")
      (footprint "STM-LQFP100_N")
      (fields (field (name "MANUFACTURER") "STMicroelectronics"))
      (libsource (lib "STMicroelectronics STM32 F4") (part "STM32F407VGT6"))
    )
    (comp (ref "U104")
      (value "MAX9923F")
      (footprint "TSSOP50P490X110-10N")
      (description "IC OPAMP CURR SENS 2.5KHZ 250V/V GAIN")
      (libsource (lib "Maxim_MAX9923F_current_sense_opamp") (part "MAX9923F-10MSOP"))
    )
    (comp (ref "U105")
      (value "Si8631AB-B-IS1")
      (footprint "SOIC127P600X175-16N")
      (description "2/1 Channel Digital Isolator")
      (libsource (lib "SL_Si8631_SOIC16") (part "SL_Si8631_NSOIC16"))
    )
    (comp (ref "U106")
      (value "LD2980CM33")
      (footprint "SOT95P280X145-5N")
      (description "IC REG LDO 3.3V 50MA SOT23-5")
      (fields (field (name "VOLTAGE") "16V"))
      (libsource (lib "3V3LDO_LD2980CM33") (part "LD2980CM33"))
    )
    (comp (ref "U107")
      (value "RT9818C-29GV")
      (footprint "SOT95P279X129-3N")
      (description "IC VOLT DETECTOR 2.9V SOT23-3")
      (libsource (lib "Richtek_RT9818C-29GV") (part "RT9818C-29GV"))
    )
    (comp (ref "U108")
      (value "AP331A")
      (footprint "SOT95P285X130-5N")
      (description "Single Channel Comparator, Open Drain, SC-74A/SOT-753")
      (libsource (lib "DI_AP331A_comparator") (part "AP331A"))
    )
    (comp (ref "U109")
      (value "MAX8212")
      (footprint "Maxim MAX8212")
      (libsource (lib "Maxim MAX8212") (part "Maxim MAX8212"))
    )
    (comp (ref "U110")
      (value "ONSEMI_NL27WZ02")
      (footprint "TSSOP50P310X90-8N")
      (description "2CH 2IN NOR")
      (libsource (lib "ONSEMI_NL27WZ02") (part "ONSEMI_NL27WZ02"))
    )
    (comp (ref "U111")
      (value "ADS7867")
      (footprint "SOT95P280X145-6N")
      (description "ADC 10BIT 240KSPS SOT23-6")
      (libsource (lib "TI_ADS7867") (part "ADS7867_SOT23-6"))
    )
    (comp (ref "U112")
      (value "ONSEMI_NL27WZ02")
      (footprint "TSSOP50P310X90-8N")
      (description "2CH 2IN NOR")
      (libsource (lib "ONSEMI_NL27WZ02") (part "ONSEMI_NL27WZ02"))
    )
    (comp (ref "U113")
      (value "TI_SN74LV08A")
      (footprint "SOIC127P600X175-14N")
      (description "AND GATE 4CH 2IN SOIC14")
      (libsource (lib "TI_SN74LV08A_SOIC14") (part "TI_SN74LV08A"))
    )
    (comp (ref "X100")
      (value "8 MHz")
      (footprint "CRYSTAL_8MHZ")
      (description "8MHz ±30ppm 20pF Crystal")
      (libsource (lib "Foxslf 8MHz Crystal") (part "XTAL_TH_8MHz"))
    )
  )
  (nets
    (net (code "5") (name "/ADC_SPI_MISO") (class "Default")
      (node (ref "TP104") (pin "1") (pinfunction "1_1") (pintype "passive"))
      (node (ref "U103") (pin "90") (pinfunction "PB4(NJTRST)_90") (pintype "bidirectional"))
      (node (ref "U105") (pin "5") (pinfunction "A3_5") (pintype "output"))
    )
    (net (code "6") (name "/ADC_SPI_SCK") (class "Default")
      (node (ref "TP103") (pin "1") (pinfunction "1_1") (pintype "passive"))
      (node (ref "U103") (pin "78") (pinfunction "PC10_78") (pintype "bidirectional"))
      (node (ref "U105") (pin "3") (pinfunction "A1_3") (pintype "input"))
    )
    (net (code "7") (name "/ADC_nCS") (class "Default")
      (node (ref "TP105") (pin "1") (pinfunction "1_1") (pintype "passive"))
      (node (ref "U103") (pin "91") (pinfunction "PB5_91") (pintype "bidirectional"))
      (node (ref "U105") (pin "4") (pinfunction "A2_4") (pintype "input"))
    )
    (net (code "8") (name "/BLU_LED") (class "Default")
      (node (ref "SB103") (pin "2") (pinfunction "2_2") (pintype "passive"))
      (node (ref "U103") (pin "25") (pinfunction "PA2_25") (pintype "bidirectional"))
    )
    (net (code "9") (name "/CAN1_N") (class "Default")
      (node (ref "D103") (pin "1") (pinfunction "1_1") (pintype "passive"))
      (node (ref "P102") (pin "5") (pinfunction "5_5") (pintype "passive"))
      (node (ref "R103") (pin "2") (pinfunction "2_2") (pintype "passive"))
      (node (ref "U101") (pin "6") (pinfunction "CANL_6") (pintype "passive"))
    )
    (net (code "10") (name "/CAN1_P") (class "Default")
      (node (ref "D105") (pin "1") (pinfunction "1_1") (pintype "passive"))
      (node (ref "P102") (pin "4") (pinfunction "4_4") (pintype "passive"))
      (node (ref "R103") (pin "1") (pinfunction "1_1") (pintype "passive"))
      (node (ref "U101") (pin "7") (pinfunction "CANH_7") (pintype "passive"))
    )
    (net (code "11") (name "/CAN1_RX") (class "Default")
      (node (ref "U101") (pin "4") (pinfunction "RXD_4") (pintype "passive"))
      (node (ref "U103") (pin "70") (pinfunction "PA11_70") (pintype "bidirectional"))
    )
    (net (code "12") (name "/CAN1_STBY") (class "Default")
      (node (ref "R106") (pin "2") (pinfunction "2_2") (pintype "passive"))
      (node (ref "U101") (pin "8") (pinfunction "STBY_8") (pintype "passive"))
      (node (ref "U103") (pin "67") (pinfunction "PA8_67") (pintype "bidirectional"))
    )
    (net (code "13") (name "/CAN1_TX") (class "Default")
      (node (ref "U101") (pin "1") (pinfunction "TXD_1") (pintype "passive"))
      (node (ref "U103") (pin "71") (pinfunction "PA12_71") (pintype "bidirectional"))
    )
    (net (code "14") (name "/CHARGE_ENABLE") (class "Default")
      (node (ref "D106") (pin "1") (pinfunction "K_1") (pintype "passive"))
      (node (ref "D108") (pin "1") (pinfunction "1_1") (pintype "passive"))
      (node (ref "P103") (pin "6") (pinfunction "6_6") (pintype "passive"))
      (node (ref "Q100") (pin "1") (pinfunction "G_1") (pintype "passive"))
      (node (ref "R102") (pin "1") (pinfunction "1_1") (pintype "passive"))
    )
    (net (code "15") (name "/CHARGE_ENABLE_SENSE") (class "Default")
      (node (ref "Q100") (pin "3") (pinfunction "D_3") (pintype "passive"))
      (node (ref "R104") (pin "1") (pinfunction "1_1") (pintype "passive"))
      (node (ref "U103") (pin "63") (pinfunction "PC6_63") (pintype "bidirectional"))
    )
    (net (code "16") (name "/CHARGE_SAFETY") (class "Default")
      (node (ref "D104") (pin "1") (pinfunction "1_1") (pintype "passive"))
      (node (ref "D112") (pin "1") (pinfunction "K_1") (pintype "passive"))
      (node (ref "P103") (pin "4") (pinfunction "4_4") (pintype "passive"))
      (node (ref "Q102") (pin "1") (pinfunction "G_1") (pintype "passive"))
      (node (ref "R110") (pin "1") (pinfunction "1_1") (pintype "passive"))
    )
    (net (code "17") (name "/CHARGE_SAFETY_SENSE") (class "Default")
      (node (ref "Q102") (pin "3") (pinfunction "D_3") (pintype "passive"))
      (node (ref "R111") (pin "1") (pinfunction "1_1") (pintype "passive"))
      (node (ref "U103") (pin "65") (pinfunction "PC8_65") (pintype "bidirectional"))
    )
    (net (code "18") (name "/CONTACTOR_ENABLE1") (class "Default")
      (node (ref "R113") (pin "1") (pinfunction "1_1") (pintype "passive"))
      (node (ref "TP109") (pin "1") (pinfunction "1_1") (pintype "passive"))
      (node (ref "U103") (pin "4") (pinfunction "PE5_4") (pintype "bidirectional"))
      (node (ref "U113") (pin "12") (pinfunction "12_12") (pintype "passive"))
    )
    (net (code "19") (name "/CONTACTOR_ENABLE2") (class "Default")
      (node (ref "R116") (pin "1") (pinfunction "1_1") (pintype "passive"))
      (node (ref "TP110") (pin "1") (pinfunction "1_1") (pintype "passive"))
      (node (ref "U103") (pin "1") (pinfunction "PE2_1") (pintype "bidirectional"))
      (node (ref "U113") (pin "4") (pinfunction "4_4") (pintype "passive"))
    )
    (net (code "20") (name "/CONTACTOR_ENABLE3") (class "Default")
      (node (ref "R114") (pin "1") (pinfunction "1_1") (pintype "passive"))
      (node (ref "TP111") (pin "1") (pinfunction "1_1") (pintype "passive"))
      (node (ref "U103") (pin "3") (pinfunction "PE4_3") (pintype "bidirectional"))
      (node (ref "U113") (pin "9") (pinfunction "9_9") (pintype "passive"))
    )
    (net (code "21") (name "/CONTACTOR_ENABLE4") (class "Default")
      (node (ref "R115") (pin "1") (pinfunction "1_1") (pintype "passive"))
      (node (ref "TP112") (pin "1") (pinfunction "1_1") (pintype "passive"))
      (node (ref "U103") (pin "2") (pinfunction "PE3_2") (pintype "bidirectional"))
      (node (ref "U113") (pin "1") (pinfunction "1_1") (pintype "passive"))
    )
    (net (code "24") (name "/CTRL1") (class "Default")
      (node (ref "U113") (pin "11") (pinfunction "11_11") (pintype "passive"))
    )
    (net (code "25") (name "/CTRL2") (class "Default")
      (node (ref "U113") (pin "6") (pinfunction "6_6") (pintype "passive"))
    )
    (net (code "26") (name "/CTRL3") (class "Default")
      (node (ref "U113") (pin "8") (pinfunction "8_8") (pintype "passive"))
    )
    (net (code "27") (name "/CTRL4") (class "Default")
      (node (ref "U113") (pin "3") (pinfunction "3_3") (pintype "passive"))
    )
    (net (code "29") (name "/CURRENT_AMP") (class "Default")
      (node (ref "C125") (pin "2") (pinfunction "2_2") (pintype "passive"))
      (node (ref "SB106") (pin "1") (pinfunction "1_1") (pintype "passive"))
      (node (ref "TP101") (pin "1") (pinfunction "1_1") (pintype "passive"))
      (node (ref "U104") (pin "9") (pinfunction "OUT_9") (pintype "passive"))
    )
    (net (code "30") (name "/CURRENT_CHECK") (class "Default")
      (node (ref "D118") (pin "1") (pinfunction "K_1") (pintype "passive"))
      (node (ref "TP113") (pin "1") (pinfunction "1_1") (pintype "passive"))
      (node (ref "U112") (pin "2") (pinfunction "2_2") (pintype "passive"))
      (node (ref "U112") (pin "3") (pinfunction "3_3") (pintype "passive"))
      (node (ref "U113") (pin "10") (pinfunction "10_10") (pintype "passive"))
      (node (ref "U113") (pin "13") (pinfunction "13_13") (pintype "passive"))
      (node (ref "U113") (pin "2") (pinfunction "2_2") (pintype "passive"))
      (node (ref "U113") (pin "5") (pinfunction "5_5") (pintype "passive"))
    )
    (net (code "31") (name "/CURRENT_SENSE_ENABLE") (class "Default")
      (node (ref "R120") (pin "2") (pinfunction "2_2") (pintype "passive"))
      (node (ref "U103") (pin "81") (pinfunction "PD0_81") (pintype "bidirectional"))
      (node (ref "U104") (pin "6") (pinfunction "~{SHDN}_6") (pintype "passive"))
    )
    (net (code "32") (name "/DISCHARGE_ENABLE") (class "Default")
      (node (ref "D107") (pin "1") (pinfunction "1_1") (pintype "passive"))
      (node (ref "D109") (pin "1") (pinfunction "K_1") (pintype "passive"))
      (node (ref "P103") (pin "5") (pinfunction "5_5") (pintype "passive"))
      (node (ref "Q101") (pin "1") (pinfunction "G_1") (pintype "passive"))
      (node (ref "R107") (pin "1") (pinfunction "1_1") (pintype "passive"))
    )
    (net (code "33") (name "/DISCHARGE_ENABLE_SENSE") (class "Default")
      (node (ref "Q101") (pin "3") (pinfunction "D_3") (pintype "passive"))
      (node (ref "R108") (pin "1") (pinfunction "1_1") (pintype "passive"))
      (node (ref "U103") (pin "64") (pinfunction "PC7_64") (pintype "bidirectional"))
    )
    (net (code "34") (name "/GRN_LED") (class "Default")
      (node (ref "SB104") (pin "2") (pinfunction "2_2") (pintype "passive"))
      (node (ref "U103") (pin "24") (pinfunction "PA1_24") (pintype "bidirectional"))
    )
    (net (code "35") (name "/HV_ENABLE") (class "Default")
      (node (ref "R121") (pin "1") (pinfunction "1_1") (pintype "passive"))
      (node (ref "U103") (pin "15") (pinfunction "PC0_15") (pintype "bidirectional"))
    )
    (net (code "36") (name "/JTDI") (class "Default")
      (node (ref "J100") (pin "8") (pinfunction "NC/TDI_8") (pintype "passive"))
      (node (ref "U103") (pin "77") (pinfunction "PA15(JTDI)_77") (pintype "bidirectional"))
    )
    (net (code "37") (name "/LATCH_RST") (class "Default")
      (node (ref "TP115") (pin "1") (pinfunction "1_1") (pintype "passive"))
      (node (ref "U110") (pin "7") (pinfunction "7_7") (pintype "passive"))
      (node (ref "U112") (pin "1") (pinfunction "1_1") (pintype "passive"))
    )
    (net (code "38") (name "/LATCH_SET") (class "Default")
      (node (ref "R126") (pin "2") (pinfunction "2_2") (pintype "passive"))
      (node (ref "TP114") (pin "1") (pinfunction "1_1") (pintype "passive"))
      (node (ref "U108") (pin "4") (pinfunction "VOUT_4") (pintype "passive"))
      (node (ref "U110") (pin "2") (pinfunction "2_2") (pintype "passive"))
      (node (ref "U112") (pin "5") (pinfunction "5_5") (pintype "passive"))
    )
    (net (code "39") (name "/NIMH_IN") (class "Default")
      (node (ref "D115") (pin "1") (pinfunction "C_1") (pintype "passive"))
      (node (ref "P104") (pin "2") (pinfunction "2_2") (pintype "passive"))
      (node (ref "Q103") (pin "1") (pinfunction "S_1") (pintype "passive"))
      (node (ref "Q103") (pin "2") (pinfunction "S_2") (pintype "passive"))
      (node (ref "Q103") (pin "3") (pinfunction "S_3") (pintype "passive"))
      (node (ref "R128") (pin "2") (pinfunction "2_2") (pintype "passive"))
      (node (ref "S101") (pin "1") (pinfunction "1_1") (pintype "passive"))
      (node (ref "S101") (pin "2") (pinfunction "2_2") (pintype "passive"))
      (node (ref "U109") (pin "8") (pinfunction "V+_8") (pintype "passive"))
    )
    (net (code "40") (name "/PWR_CURRENT_SENSE") (class "Default")
      (node (ref "R124") (pin "2") (pinfunction "2_2") (pintype "passive"))
      (node (ref "SB106") (pin "2") (pinfunction "2_2") (pintype "passive"))
      (node (ref "TP100") (pin "1") (pinfunction "1_1") (pintype "passive"))
      (node (ref "U103") (pin "16") (pinfunction "PC1_16") (pintype "bidirectional"))
      (node (ref "U108") (pin "3") (pinfunction "+_3") (pintype "passive"))
    )
    (net (code "41") (name "/RED_LED") (class "Default")
      (node (ref "SB105") (pin "2") (pinfunction "2_2") (pintype "passive"))
      (node (ref "U103") (pin "23") (pinfunction "PA0-WKUP(PA0)_23") (pintype "bidirectional"))
    )
    (net (code "42") (name "/SENSE1") (class "Default")
      (node (ref "U103") (pin "98") (pinfunction "PE1_98") (pintype "bidirectional"))
    )
    (net (code "43") (name "/SENSE2") (class "Default")
      (node (ref "U103") (pin "97") (pinfunction "PE0_97") (pintype "bidirectional"))
    )
    (net (code "44") (name "/SENSE3") (class "Default")
      (node (ref "U103") (pin "96") (pinfunction "PB9_96") (pintype "bidirectional"))
    )
    (net (code "45") (name "/SENSE4") (class "Default")
      (node (ref "U103") (pin "95") (pinfunction "PB8_95") (pintype "bidirectional"))
    )
    (net (code "47") (name "/SOFT_RESET") (class "Default")
      (node (ref "D117") (pin "1") (pinfunction "1_1") (pintype "passive"))
      (node (ref "R127") (pin "2") (pinfunction "2_2") (pintype "passive"))
      (node (ref "S102") (pin "3") (pinfunction "3_3") (pintype "passive"))
      (node (ref "S102") (pin "4") (pinfunction "4_4") (pintype "passive"))
      (node (ref "U103") (pin "5") (pinfunction "PE6_5") (pintype "bidirectional"))
      (node (ref "U107") (pin "1") (pinfunction "~{RESET}_1") (pintype "passive"))
      (node (ref "U110") (pin "1") (pinfunction "1_1") (pintype "passive"))
    )
    (net (code "48") (name "/SWDCLK") (class "Default")
      (node (ref "J100") (pin "4") (pinfunction "SWDCLK/TCK_4") (pintype "passive"))
      (node (ref "U103") (pin "76") (pinfunction "PA14(JTCK-SWCLK)_76") (pintype "bidirectional"))
    )
    (net (code "49") (name "/SWDIO") (class "Default")
      (node (ref "J100") (pin "2") (pinfunction "SWDIO/TMS_2") (pintype "passive"))
      (node (ref "U103") (pin "72") (pinfunction "PA13(JTMS-SWDIO)_72") (pintype "bidirectional"))
    )
    (net (code "50") (name "/SWO") (class "Default")
      (node (ref "J100") (pin "6") (pinfunction "SWO/TDO_6") (pintype "passive"))
      (node (ref "U103") (pin "89") (pinfunction "PB3(JTDO/TRACESWO)_89") (pintype "bidirectional"))
    )
    (net (code "51") (name "/TRIM") (class "Default")
      (node (ref "R123") (pin "3") (pinfunction "3_3") (pintype "passive"))
      (node (ref "TP107") (pin "1") (pinfunction "1_1") (pintype "passive"))
      (node (ref "U108") (pin "1") (pinfunction "-_1") (pintype "passive"))
    )
    (net (code "52") (name "/UART3_RX") (class "Default")
      (node (ref "P101") (pin "2") (pinfunction "2_2") (pintype "passive"))
      (node (ref "U103") (pin "48") (pinfunction "PB11_48") (pintype "bidirectional"))
    )
    (net (code "53") (name "/UART3_TX") (class "Default")
      (node (ref "P101") (pin "3") (pinfunction "3_3") (pintype "passive"))
      (node (ref "U103") (pin "47") (pinfunction "PB10_47") (pintype "bidirectional"))
    )
    (net (code "54") (name "/nRESET") (class "Default")
      (node (ref "C100") (pin "2") (pinfunction "2_2") (pintype "passive"))
      (node (ref "D101") (pin "1") (pinfunction "1_1") (pintype "passive"))
      (node (ref "J100") (pin "10") (pinfunction "~{RESET}_10") (pintype "passive"))
      (node (ref "R100") (pin "1") (pinfunction "1_1") (pintype "passive"))
      (node (ref "S100") (pin "3") (pinfunction "3_3") (pintype "passive"))
      (node (ref "S100") (pin "4") (pinfunction "4_4") (pintype "passive"))
      (node (ref "U103") (pin "14") (pinfunction "NRST_14") (pintype "bidirectional"))
    )
    (net (code "55") (name "3V3") (class "Default")
      (node (ref "C101") (pin "2") (pinfunction "2_2") (pintype "passive"))
      (node (ref "C107") (pin "1") (pinfunction "1_1") (pintype "passive"))
      (node (ref "C108") (pin "2") (pinfunction "2_2") (pintype "passive"))
      (node (ref "C109") (pin "2") (pinfunction "2_2") (pintype "passive"))
      (node (ref "C110") (pin "2") (pinfunction "2_2") (pintype "passive"))
      (node (ref "C111") (pin "2") (pinfunction "2_2") (pintype "passive"))
      (node (ref "C112") (pin "2") (pinfunction "2_2") (pintype "passive"))
      (node (ref "C113") (pin "2") (pinfunction "2_2") (pintype "passive"))
      (node (ref "C114") (pin "2") (pinfunction "2_2") (pintype "passive"))
      (node (ref "C115") (pin "2") (pinfunction "2_2") (pintype "passive"))
      (node (ref "C122") (pin "2") (pinfunction "2_2") (pintype "passive"))
      (node (ref "C123") (pin "2") (pinfunction "2_2") (pintype "passive"))
      (node (ref "C124") (pin "2") (pinfunction "2_2") (pintype "passive"))
      (node (ref "C129") (pin "2") (pinfunction "2_2") (pintype "passive"))
      (node (ref "C133") (pin "2") (pinfunction "2_2") (pintype "passive"))
      (node (ref "C135") (pin "2") (pinfunction "2_2") (pintype "passive"))
      (node (ref "C136") (pin "2") (pinfunction "2_2") (pintype "passive"))
      (node (ref "D114") (pin "1") (pinfunction "Red_1") (pintype "passive"))
      (node (ref "FB100") (pin "1") (pinfunction "1_1") (pintype "passive"))
      (node (ref "J100") (pin "1") (pinfunction "VREF_1") (pintype "passive"))
      (node (ref "R100") (pin "2") (pinfunction "2_2") (pintype "passive"))
      (node (ref "R102") (pin "2") (pinfunction "2_2") (pintype "passive"))
      (node (ref "R104") (pin "2") (pinfunction "2_2") (pintype "passive"))
      (node (ref "R107") (pin "2") (pinfunction "2_2") (pintype "passive"))
      (node (ref "R108") (pin "2") (pinfunction "2_2") (pintype "passive"))
      (node (ref "R110") (pin "2") (pinfunction "2_2") (pintype "passive"))
      (node (ref "R111") (pin "2") (pinfunction "2_2") (pintype "passive"))
      (node (ref "R112") (pin "1") (pinfunction "1_1") (pintype "passive"))
      (node (ref "R123") (pin "1") (pinfunction "1_1") (pintype "passive"))
      (node (ref "R126") (pin "1") (pinfunction "1_1") (pintype "passive"))
      (node (ref "R127") (pin "1") (pinfunction "1_1") (pintype "passive"))
      (node (ref "R131") (pin "1") (pinfunction "1_1") (pintype "passive"))
      (node (ref "SB100") (pin "2") (pinfunction "2_2") (pintype "passive"))
      (node (ref "SB101") (pin "2") (pinfunction "2_2") (pintype "passive"))
      (node (ref "SB102") (pin "2") (pinfunction "2_2") (pintype "passive"))
      (node (ref "U101") (pin "5") (pinfunction "VIO_5") (pintype "passive"))
      (node (ref "U102") (pin "1") (pinfunction "OUT_1") (pintype "power_in"))
      (node (ref "U103") (pin "100") (pinfunction "VDD_100") (pintype "power_in"))
      (node (ref "U103") (pin "11") (pinfunction "VDD_11") (pintype "power_in"))
      (node (ref "U103") (pin "19") (pinfunction "VDD_19") (pintype "power_in"))
      (node (ref "U103") (pin "28") (pinfunction "VDD_28") (pintype "power_in"))
      (node (ref "U103") (pin "50") (pinfunction "VDD_50") (pintype "power_in"))
      (node (ref "U103") (pin "6") (pinfunction "VBAT_6") (pintype "power_in"))
      (node (ref "U103") (pin "75") (pinfunction "VDD_75") (pintype "power_in"))
      (node (ref "U104") (pin "10") (pinfunction "VDD_10") (pintype "passive"))
      (node (ref "U105") (pin "1") (pinfunction "VDD1_1") (pintype "power_in"))
      (node (ref "U105") (pin "7") (pinfunction "EN1_7") (pintype "passive"))
      (node (ref "U107") (pin "3") (pinfunction "VDD_3") (pintype "passive"))
      (node (ref "U108") (pin "5") (pinfunction "VCC_5") (pintype "passive"))
      (node (ref "U110") (pin "8") (pinfunction "VCC_8") (pintype "passive"))
      (node (ref "U112") (pin "8") (pinfunction "VCC_8") (pintype "passive"))
      (node (ref "U113") (pin "14") (pinfunction "VCC_14") (pintype "passive"))
    )
    (net (code "56") (name "3V3_ISO") (class "Default")
      (node (ref "C127") (pin "2") (pinfunction "2_2") (pintype "passive"))
      (node (ref "C130") (pin "2") (pinfunction "2_2") (pintype "passive"))
      (node (ref "C131") (pin "2") (pinfunction "2_2") (pintype "passive"))
      (node (ref "C132") (pin "2") (pinfunction "2_2") (pintype "passive"))
      (node (ref "R125") (pin "2") (pinfunction "2_2") (pintype "passive"))
      (node (ref "U105") (pin "10") (pinfunction "EN2_10") (pintype "passive"))
      (node (ref "U105") (pin "16") (pinfunction "VDD2_16") (pintype "power_in"))
      (node (ref "U106") (pin "5") (pinfunction "OUT_5") (pintype "power_in"))
      (node (ref "U111") (pin "1") (pinfunction "REF/VDD_1") (pintype "power_in"))
    )
    (net (code "57") (name "5V") (class "Default")
      (node (ref "C102") (pin "2") (pinfunction "2_2") (pintype "passive"))
      (node (ref "C103") (pin "2") (pinfunction "2_2") (pintype "passive"))
      (node (ref "C104") (pin "2") (pinfunction "2_2") (pintype "passive"))
      (node (ref "C105") (pin "2") (pinfunction "2_2") (pintype "passive"))
      (node (ref "D110") (pin "1") (pinfunction "1_1") (pintype "passive"))
      (node (ref "D111") (pin "1") (pinfunction "1_1") (pintype "passive"))
      (node (ref "U101") (pin "3") (pinfunction "VDD_3") (pintype "passive"))
      (node (ref "U102") (pin "4") (pinfunction "EN_4") (pintype "passive"))
      (node (ref "U102") (pin "6") (pinfunction "IN_6") (pintype "power_in"))
    )
    (net (code "58") (name "5V_DCDC") (class "Default")
      (node (ref "D111") (pin "2") (pinfunction "2_2") (pintype "passive"))
      (node (ref "U100") (pin "3") (pinfunction "VOUT_3") (pintype "passive"))
    )
    (net (code "59") (name "5V_UART") (class "Default")
      (node (ref "D110") (pin "2") (pinfunction "2_2") (pintype "passive"))
      (node (ref "P101") (pin "1") (pinfunction "1_1") (pintype "passive"))
    )
    (net (code "60") (name "12V_CAN") (class "Default")
      (node (ref "D102") (pin "1") (pinfunction "C_1") (pintype "passive"))
      (node (ref "P102") (pin "1") (pinfunction "1_1") (pintype "passive"))
      (node (ref "U100") (pin "1") (pinfunction "VIN_1") (pintype "passive"))
    )
    (net (code "61") (name "12V_CONTACTOR") (class "Default")
      (node (ref "R122") (pin "2") (pinfunction "2_2") (pintype "passive"))
      (node (ref "TP119") (pin "1") (pinfunction "1_1") (pintype "passive"))
      (node (ref "U104") (pin "3") (pinfunction "RS-_3") (pintype "power_in"))
    )
    (net (code "62") (name "12V_PWR") (class "Default")
      (node (ref "D100") (pin "1") (pinfunction "C_1") (pintype "passive"))
      (node (ref "P100") (pin "2") (pinfunction "2_2") (pintype "passive"))
      (node (ref "R122") (pin "1") (pinfunction "1_1") (pintype "passive"))
      (node (ref "TP118") (pin "1") (pinfunction "1_1") (pintype "passive"))
      (node (ref "U104") (pin "1") (pinfunction "RSB_1") (pintype "passive"))
      (node (ref "U104") (pin "2") (pinfunction "RS+_2") (pintype "power_in"))
    )
    (net (code "63") (name "GND") (class "Default")
      (node (ref "C100") (pin "1") (pinfunction "1_1") (pintype "passive"))
      (node (ref "C101") (pin "1") (pinfunction "1_1") (pintype "passive"))
      (node (ref "C102") (pin "1") (pinfunction "1_1") (pintype "passive"))
      (node (ref "C103") (pin "1") (pinfunction "1_1") (pintype "passive"))
      (node (ref "C104") (pin "1") (pinfunction "1_1") (pintype "passive"))
      (node (ref "C105") (pin "1") (pinfunction "1_1") (pintype "passive"))
      (node (ref "C106") (pin "1") (pinfunction "1_1") (pintype "passive"))
      (node (ref "C107") (pin "2") (pinfunction "2_2") (pintype "passive"))
      (node (ref "C108") (pin "1") (pinfunction "1_1") (pintype "passive"))
      (node (ref "C109") (pin "1") (pinfunction "1_1") (pintype "passive"))
      (node (ref "C110") (pin "1") (pinfunction "1_1") (pintype "passive"))
      (node (ref "C111") (pin "1") (pinfunction "1_1") (pintype "passive"))
      (node (ref "C112") (pin "1") (pinfunction "1_1") (pintype "passive"))
      (node (ref "C113") (pin "1") (pinfunction "1_1") (pintype "passive"))
      (node (ref "C114") (pin "1") (pinfunction "1_1") (pintype "passive"))
      (node (ref "C115") (pin "1") (pinfunction "1_1") (pintype "passive"))
      (node (ref "C116") (pin "1") (pinfunction "1_1") (pintype "passive"))
      (node (ref "C117") (pin "1") (pinfunction "1_1") (pintype "passive"))
      (node (ref "C118") (pin "1") (pinfunction "1_1") (pintype "passive"))
      (node (ref "C119") (pin "1") (pinfunction "1_1") (pintype "passive"))
      (node (ref "C120") (pin "1") (pinfunction "1_1") (pintype "passive"))
      (node (ref "C121") (pin "1") (pinfunction "1_1") (pintype "passive"))
      (node (ref "C122") (pin "1") (pinfunction "1_1") (pintype "passive"))
      (node (ref "C123") (pin "1") (pinfunction "1_1") (pintype "passive"))
      (node (ref "C124") (pin "1") (pinfunction "1_1") (pintype "passive"))
      (node (ref "C129") (pin "1") (pinfunction "1_1") (pintype "passive"))
      (node (ref "C133") (pin "1") (pinfunction "1_1") (pintype "passive"))
      (node (ref "C135") (pin "1") (pinfunction "1_1") (pintype "passive"))
      (node (ref "C136") (pin "1") (pinfunction "1_1") (pintype "passive"))
      (node (ref "D100") (pin "2") (pinfunction "A_2") (pintype "passive"))
      (node (ref "D101") (pin "2") (pinfunction "2_2") (pintype "passive"))
      (node (ref "D102") (pin "2") (pinfunction "A_2") (pintype "passive"))
      (node (ref "D103") (pin "2") (pinfunction "2_2") (pintype "passive"))
      (node (ref "D104") (pin "2") (pinfunction "2_2") (pintype "passive"))
      (node (ref "D105") (pin "2") (pinfunction "2_2") (pintype "passive"))
      (node (ref "D107") (pin "2") (pinfunction "2_2") (pintype "passive"))
      (node (ref "D108") (pin "2") (pinfunction "2_2") (pintype "passive"))
      (node (ref "D113") (pin "1") (pinfunction "K_1") (pintype "passive"))
      (node (ref "D117") (pin "2") (pinfunction "2_2") (pintype "passive"))
      (node (ref "FB101") (pin "2") (pinfunction "2_2") (pintype "passive"))
      (node (ref "J100") (pin "3") (pinfunction "GND_3") (pintype "passive"))
      (node (ref "J100") (pin "5") (pinfunction "GND_5") (pintype "passive"))
      (node (ref "J100") (pin "9") (pinfunction "GNDdetect_9") (pintype "passive"))
      (node (ref "K100") (pin "2") (pinfunction "Control_-_2") (pintype "passive"))
      (node (ref "P100") (pin "1") (pinfunction "1_1") (pintype "passive"))
      (node (ref "P100") (pin "3") (pinfunction "3_3") (pintype "passive"))
      (node (ref "P101") (pin "4") (pinfunction "4_4") (pintype "passive"))
      (node (ref "P102") (pin "2") (pinfunction "2_2") (pintype "passive"))
      (node (ref "P102") (pin "3") (pinfunction "3_3") (pintype "passive"))
      (node (ref "P102") (pin "6") (pinfunction "6_6") (pintype "passive"))
      (node (ref "P103") (pin "1") (pinfunction "1_1") (pintype "passive"))
      (node (ref "P103") (pin "2") (pinfunction "2_2") (pintype "passive"))
      (node (ref "P103") (pin "3") (pinfunction "3_3") (pintype "passive"))
      (node (ref "Q100") (pin "2") (pinfunction "S_2") (pintype "passive"))
      (node (ref "Q101") (pin "2") (pinfunction "S_2") (pintype "passive"))
      (node (ref "Q102") (pin "2") (pinfunction "S_2") (pintype "passive"))
      (node (ref "R106") (pin "1") (pinfunction "1_1") (pintype "passive"))
      (node (ref "R113") (pin "2") (pinfunction "2_2") (pintype "passive"))
      (node (ref "R114") (pin "2") (pinfunction "2_2") (pintype "passive"))
      (node (ref "R115") (pin "2") (pinfunction "2_2") (pintype "passive"))
      (node (ref "R116") (pin "2") (pinfunction "2_2") (pintype "passive"))
      (node (ref "R120") (pin "1") (pinfunction "1_1") (pintype "passive"))
      (node (ref "R123") (pin "2") (pinfunction "2_2") (pintype "passive"))
      (node (ref "R124") (pin "1") (pinfunction "1_1") (pintype "passive"))
      (node (ref "S100") (pin "1") (pinfunction "1_1") (pintype "passive"))
      (node (ref "S100") (pin "2") (pinfunction "2_2") (pintype "passive"))
      (node (ref "S102") (pin "1") (pinfunction "1_1") (pintype "passive"))
      (node (ref "S102") (pin "2") (pinfunction "2_2") (pintype "passive"))
      (node (ref "TP102") (pin "1") (pinfunction "1_1") (pintype "passive"))
      (node (ref "TP106") (pin "1") (pinfunction "1_1") (pintype "passive"))
      (node (ref "TP108") (pin "1") (pinfunction "1_1") (pintype "passive"))
      (node (ref "TP116") (pin "1") (pinfunction "1_1") (pintype "passive"))
      (node (ref "TP117") (pin "1") (pinfunction "1_1") (pintype "passive"))
      (node (ref "U100") (pin "2") (pinfunction "GND_2") (pintype "passive"))
      (node (ref "U101") (pin "2") (pinfunction "VSS_2") (pintype "passive"))
      (node (ref "U102") (pin "3") (pinfunction "GND_3") (pintype "power_in"))
      (node (ref "U102") (pin "7") (pinfunction "EPAD_7") (pintype "passive"))
      (node (ref "U103") (pin "10") (pinfunction "VSS_10") (pintype "power_in"))
      (node (ref "U103") (pin "27") (pinfunction "VSS_27") (pintype "power_in"))
      (node (ref "U103") (pin "74") (pinfunction "VSS_74") (pintype "power_in"))
      (node (ref "U103") (pin "94") (pinfunction "BOOT0_94") (pintype "input"))
      (node (ref "U103") (pin "99") (pinfunction "VSS_99") (pintype "power_in"))
      (node (ref "U104") (pin "5") (pinfunction "GND_5") (pintype "passive"))
      (node (ref "U104") (pin "7") (pinfunction "REF_7") (pintype "passive"))
      (node (ref "U105") (pin "2") (pinfunction "GND1_2") (pintype "power_in"))
      (node (ref "U105") (pin "8") (pinfunction "GND1_8") (pintype "power_in"))
      (node (ref "U107") (pin "2") (pinfunction "GND_2") (pintype "passive"))
      (node (ref "U108") (pin "2") (pinfunction "GND_2") (pintype "passive"))
      (node (ref "U110") (pin "4") (pinfunction "GND_4") (pintype "passive"))
      (node (ref "U112") (pin "4") (pinfunction "GND_4") (pintype "passive"))
      (node (ref "U113") (pin "7") (pinfunction "GND_7") (pintype "passive"))
    )
    (net (code "64") (name "GND_ISO") (class "Default")
      (node (ref "C126") (pin "1") (pinfunction "1_1") (pintype "passive"))
      (node (ref "C127") (pin "1") (pinfunction "1_1") (pintype "passive"))
      (node (ref "C128") (pin "1") (pinfunction "1_1") (pintype "passive"))
      (node (ref "C130") (pin "1") (pinfunction "1_1") (pintype "passive"))
      (node (ref "C131") (pin "1") (pinfunction "1_1") (pintype "passive"))
      (node (ref "C132") (pin "1") (pinfunction "1_1") (pintype "passive"))
      (node (ref "C134") (pin "1") (pinfunction "1_1") (pintype "passive"))
      (node (ref "D115") (pin "2") (pinfunction "A_2") (pintype "passive"))
      (node (ref "D116") (pin "2") (pinfunction "A_2") (pintype "passive"))
      (node (ref "D119") (pin "2") (pinfunction "A_2") (pintype "passive"))
      (node (ref "P104") (pin "1") (pinfunction "1_1") (pintype "passive"))
      (node (ref "P104") (pin "3") (pinfunction "3_3") (pintype "passive"))
      (node (ref "P106") (pin "1") (pinfunction "1_1") (pintype "passive"))
      (node (ref "P106") (pin "3") (pinfunction "3_3") (pintype "passive"))
      (node (ref "R130") (pin "1") (pinfunction "1_1") (pintype "passive"))
      (node (ref "R134") (pin "2") (pinfunction "2_2") (pintype "passive"))
      (node (ref "U105") (pin "15") (pinfunction "GND2_15") (pintype "power_in"))
      (node (ref "U105") (pin "9") (pinfunction "GND2_9") (pintype "power_in"))
      (node (ref "U106") (pin "2") (pinfunction "GND_2") (pintype "power_in"))
      (node (ref "U109") (pin "5") (pinfunction "GND_5") (pintype "passive"))
      (node (ref "U111") (pin "2") (pinfunction "GND_2") (pintype "power_in"))
    )
    (net (code "65") (name "NIMH_OUT") (class "Default")
      (node (ref "C126") (pin "2") (pinfunction "2_2") (pintype "passive"))
      (node (ref "C128") (pin "2") (pinfunction "2_2") (pintype "passive"))
      (node (ref "D119") (pin "1") (pinfunction "C_1") (pintype "passive"))
      (node (ref "P106") (pin "2") (pinfunction "2_2") (pintype "passive"))
      (node (ref "Q103") (pin "5") (pinfunction "D_5") (pintype "passive"))
      (node (ref "Q103") (pin "6") (pinfunction "D_6") (pintype "passive"))
      (node (ref "Q103") (pin "7") (pinfunction "D_7") (pintype "passive"))
      (node (ref "Q103") (pin "8") (pinfunction "D_8") (pintype "passive"))
      (node (ref "R132") (pin "2") (pinfunction "2_2") (pintype "passive"))
      (node (ref "R133") (pin "2") (pinfunction "2_2") (pintype "passive"))
      (node (ref "U106") (pin "1") (pinfunction "IN_1") (pintype "power_in"))
      (node (ref "U106") (pin "3") (pinfunction "EN_3") (pintype "input"))
    )
    (net (code "66") (name "Net-(D106-A)") (class "Default")
      (node (ref "D106") (pin "2") (pinfunction "A_2") (pintype "passive"))
      (node (ref "R101") (pin "2") (pinfunction "2_2") (pintype "passive"))
    )
    (net (code "67") (name "Net-(D109-A)") (class "Default")
      (node (ref "D109") (pin "2") (pinfunction "A_2") (pintype "passive"))
      (node (ref "R105") (pin "2") (pinfunction "2_2") (pintype "passive"))
    )
    (net (code "68") (name "Net-(D112-A)") (class "Default")
      (node (ref "D112") (pin "2") (pinfunction "A_2") (pintype "passive"))
      (node (ref "R109") (pin "2") (pinfunction "2_2") (pintype "passive"))
    )
    (net (code "69") (name "Net-(D113-A)") (class "Default")
      (node (ref "D113") (pin "2") (pinfunction "A_2") (pintype "passive"))
      (node (ref "R112") (pin "2") (pinfunction "2_2") (pintype "passive"))
    )
    (net (code "70") (name "Net-(D114-Blue)") (class "Default")
      (node (ref "D114") (pin "3") (pinfunction "Blue_3") (pintype "passive"))
      (node (ref "R118") (pin "1") (pinfunction "1_1") (pintype "passive"))
    )
    (net (code "71") (name "Net-(D114-Green)") (class "Default")
      (node (ref "D114") (pin "2") (pinfunction "Green_2") (pintype "passive"))
      (node (ref "R117") (pin "1") (pinfunction "1_1") (pintype "passive"))
    )
    (net (code "72") (name "Net-(D114-Pad4)") (class "Default")
      (node (ref "D114") (pin "4") (pinfunction "4_4") (pintype "passive"))
      (node (ref "R119") (pin "1") (pinfunction "1_1") (pintype "passive"))
    )
    (net (code "73") (name "Net-(D116-C)") (class "Default")
      (node (ref "D116") (pin "1") (pinfunction "C_1") (pintype "passive"))
      (node (ref "R133") (pin "1") (pinfunction "1_1") (pintype "passive"))
      (node (ref "R134") (pin "1") (pinfunction "1_1") (pintype "passive"))
      (node (ref "S101") (pin "3") (pinfunction "3_3") (pintype "passive"))
      (node (ref "S101") (pin "4") (pinfunction "4_4") (pintype "passive"))
      (node (ref "U109") (pin "3") (pinfunction "THRESH_3") (pintype "passive"))
    )
    (net (code "74") (name "Net-(D118-A)") (class "Default")
      (node (ref "D118") (pin "2") (pinfunction "A_2") (pintype "passive"))
      (node (ref "R131") (pin "2") (pinfunction "2_2") (pintype "passive"))
    )
    (net (code "75") (name "Net-(K100-Control_+)") (class "Default")
      (node (ref "K100") (pin "1") (pinfunction "Control_+_1") (pintype "passive"))
      (node (ref "R121") (pin "2") (pinfunction "2_2") (pintype "passive"))
    )
    (net (code "76") (name "Net-(K100-Load-Pad3)") (class "Default")
      (node (ref "K100") (pin "3") (pinfunction "Load_3") (pintype "passive"))
      (node (ref "P105") (pin "2") (pinfunction "2_2") (pintype "passive"))
    )
    (net (code "77") (name "Net-(K100-Load-Pad4)") (class "Default")
      (node (ref "K100") (pin "4") (pinfunction "Load_4") (pintype "passive"))
      (node (ref "P105") (pin "1") (pinfunction "1_1") (pintype "passive"))
    )
    (net (code "78") (name "Net-(Q103-G)") (class "Default")
      (node (ref "Q103") (pin "4") (pinfunction "G_4") (pintype "passive"))
      (node (ref "R129") (pin "2") (pinfunction "2_2") (pintype "passive"))
    )
    (net (code "79") (name "Net-(R101-Pad1)") (class "Default")
      (node (ref "R101") (pin "1") (pinfunction "1_1") (pintype "passive"))
      (node (ref "SB100") (pin "1") (pinfunction "1_1") (pintype "passive"))
    )
    (net (code "80") (name "Net-(R105-Pad1)") (class "Default")
      (node (ref "R105") (pin "1") (pinfunction "1_1") (pintype "passive"))
      (node (ref "SB101") (pin "1") (pinfunction "1_1") (pintype "passive"))
    )
    (net (code "81") (name "Net-(R109-Pad1)") (class "Default")
      (node (ref "R109") (pin "1") (pinfunction "1_1") (pintype "passive"))
      (node (ref "SB102") (pin "1") (pinfunction "1_1") (pintype "passive"))
    )
    (net (code "82") (name "Net-(R117-Pad2)") (class "Default")
      (node (ref "R117") (pin "2") (pinfunction "2_2") (pintype "passive"))
      (node (ref "SB103") (pin "1") (pinfunction "1_1") (pintype "passive"))
    )
    (net (code "83") (name "Net-(R118-Pad2)") (class "Default")
      (node (ref "R118") (pin "2") (pinfunction "2_2") (pintype "passive"))
      (node (ref "SB104") (pin "1") (pinfunction "1_1") (pintype "passive"))
    )
    (net (code "84") (name "Net-(R119-Pad2)") (class "Default")
      (node (ref "R119") (pin "2") (pinfunction "2_2") (pintype "passive"))
      (node (ref "SB105") (pin "1") (pinfunction "1_1") (pintype "passive"))
    )
    (net (code "85") (name "Net-(U102-NR)") (class "Default")
      (node (ref "C106") (pin "2") (pinfunction "2_2") (pintype "passive"))
      (node (ref "U102") (pin "2") (pinfunction "NR_2") (pintype "passive"))
    )
    (net (code "86") (name "Net-(U103A-PH0-OSC_IN(PH0))") (class "Default")
      (node (ref "C120") (pin "2") (pinfunction "2_2") (pintype "passive"))
      (node (ref "U103") (pin "12") (pinfunction "PH0-OSC_IN(PH0)_12") (pintype "bidirectional"))
      (node (ref "X100") (pin "2") (pintype "passive"))
    )
    (net (code "87") (name "Net-(U103A-PH1-OSC_OUT(PH1))") (class "Default")
      (node (ref "C121") (pin "2") (pinfunction "2_2") (pintype "passive"))
      (node (ref "U103") (pin "13") (pinfunction "PH1-OSC_OUT(PH1)_13") (pintype "bidirectional"))
      (node (ref "X100") (pin "1") (pintype "passive"))
    )
    (net (code "88") (name "Net-(U103A-VCAP_1)") (class "Default")
      (node (ref "C119") (pin "2") (pinfunction "2_2") (pintype "passive"))
      (node (ref "U103") (pin "49") (pinfunction "VCAP_1_49") (pintype "power_in"))
    )
    (net (code "89") (name "Net-(U103A-VCAP_2)") (class "Default")
      (node (ref "C117") (pin "2") (pinfunction "2_2") (pintype "passive"))
      (node (ref "U103") (pin "73") (pinfunction "VCAP_2_73") (pintype "power_in"))
    )
    (net (code "90") (name "Net-(U103B-VSSA)") (class "Default")
      (node (ref "FB101") (pin "1") (pinfunction "1_1") (pintype "passive"))
      (node (ref "U103") (pin "20") (pinfunction "VSSA_20") (pintype "power_in"))
    )
    (net (code "91") (name "Net-(U104-FB)") (class "Default")
      (node (ref "C125") (pin "1") (pinfunction "1_1") (pintype "passive"))
      (node (ref "U104") (pin "8") (pinfunction "FB_8") (pintype "passive"))
    )
    (net (code "92") (name "Net-(U105-B1)") (class "Default")
      (node (ref "U105") (pin "14") (pinfunction "B1_14") (pintype "output"))
      (node (ref "U111") (pin "4") (pinfunction "SCLK_4") (pintype "input"))
    )
    (net (code "93") (name "Net-(U105-B2)") (class "Default")
      (node (ref "R125") (pin "1") (pinfunction "1_1") (pintype "passive"))
      (node (ref "U105") (pin "13") (pinfunction "B2_13") (pintype "output"))
      (node (ref "U111") (pin "6") (pinfunction "~{CS}_6") (pintype "input"))
    )
    (net (code "94") (name "Net-(U105-B3)") (class "Default")
      (node (ref "U105") (pin "12") (pinfunction "B3_12") (pintype "input"))
      (node (ref "U111") (pin "5") (pinfunction "SDO_5") (pintype "output"))
    )
    (net (code "95") (name "Net-(U109-OUT)") (class "Default")
      (node (ref "R128") (pin "1") (pinfunction "1_1") (pintype "passive"))
      (node (ref "R129") (pin "1") (pinfunction "1_1") (pintype "passive"))
      (node (ref "U109") (pin "4") (pinfunction "OUT_4") (pintype "passive"))
    )
    (net (code "96") (name "Net-(U111-VIN)") (class "Default")
      (node (ref "C134") (pin "2") (pinfunction "2_2") (pintype "passive"))
      (node (ref "R130") (pin "2") (pinfunction "2_2") (pintype "passive"))
      (node (ref "R132") (pin "1") (pinfunction "1_1") (pintype "passive"))
      (node (ref "U111") (pin "3") (pinfunction "VIN_3") (pintype "input"))
    )
    (net (code "97") (name "Net-(U112-Pad6)") (class "Default")
      (node (ref "U112") (pin "6") (pinfunction "6_6") (pintype "passive"))
      (node (ref "U112") (pin "7") (pinfunction "7_7") (pintype "passive"))
    )
    (net (code "98") (name "VDDA") (class "Default")
      (node (ref "C116") (pin "2") (pinfunction "2_2") (pintype "passive"))
      (node (ref "C118") (pin "2") (pinfunction "2_2") (pintype "passive"))
      (node (ref "FB100") (pin "2") (pinfunction "2_2") (pintype "passive"))
      (node (ref "U103") (pin "21") (pinfunction "VREF+_21") (pintype "power_in"))
      (node (ref "U103") (pin "22") (pinfunction "VDDA_22") (pintype "power_in"))
    )
    (net (code "99") (name "unconnected-(J100-KEY-Pad7)") (class "Default")
      (node (ref "J100") (pin "7") (pinfunction "KEY_7") (pintype "passive"))
    )
    (net (code "100") (name "unconnected-(U102-NC-Pad5)") (class "Default")
      (node (ref "U102") (pin "5") (pinfunction "NC_5") (pintype "passive+no_connect"))
    )
    (net (code "101") (name "unconnected-(U103A-PA3-Pad26)") (class "Default")
      (node (ref "U103") (pin "26") (pinfunction "PA3_26") (pintype "bidirectional"))
    )
    (net (code "102") (name "unconnected-(U103A-PA4-Pad29)") (class "Default")
      (node (ref "U103") (pin "29") (pinfunction "PA4_29") (pintype "bidirectional"))
    )
    (net (code "103") (name "unconnected-(U103A-PA5-Pad30)") (class "Default")
      (node (ref "U103") (pin "30") (pinfunction "PA5_30") (pintype "bidirectional"))
    )
    (net (code "104") (name "unconnected-(U103A-PA6-Pad31)") (class "Default")
      (node (ref "U103") (pin "31") (pinfunction "PA6_31") (pintype "bidirectional"))
    )
    (net (code "105") (name "unconnected-(U103A-PA7-Pad32)") (class "Default")
      (node (ref "U103") (pin "32") (pinfunction "PA7_32") (pintype "bidirectional"))
    )
    (net (code "106") (name "unconnected-(U103A-PA9-Pad68)") (class "Default")
      (node (ref "U103") (pin "68") (pinfunction "PA9_68") (pintype "bidirectional"))
    )
    (net (code "107") (name "unconnected-(U103A-PA10-Pad69)") (class "Default")
      (node (ref "U103") (pin "69") (pinfunction "PA10_69") (pintype "bidirectional"))
    )
    (net (code "108") (name "unconnected-(U103A-PB0-Pad35)") (class "Default")
      (node (ref "U103") (pin "35") (pinfunction "PB0_35") (pintype "bidirectional"))
    )
    (net (code "109") (name "unconnected-(U103A-PB1-Pad36)") (class "Default")
      (node (ref "U103") (pin "36") (pinfunction "PB1_36") (pintype "bidirectional"))
    )
    (net (code "110") (name "unconnected-(U103A-PB2-BOOT1(PB2)-Pad37)") (class "Default")
      (node (ref "U103") (pin "37") (pinfunction "PB2-BOOT1(PB2)_37") (pintype "bidirectional"))
    )
    (net (code "111") (name "unconnected-(U103A-PB6-Pad92)") (class "Default")
      (node (ref "U103") (pin "92") (pinfunction "PB6_92") (pintype "bidirectional"))
    )
    (net (code "112") (name "unconnected-(U103A-PB7-Pad93)") (class "Default")
      (node (ref "U103") (pin "93") (pinfunction "PB7_93") (pintype "bidirectional"))
    )
    (net (code "113") (name "unconnected-(U103A-PB12-Pad51)") (class "Default")
      (node (ref "U103") (pin "51") (pinfunction "PB12_51") (pintype "bidirectional"))
    )
    (net (code "114") (name "unconnected-(U103A-PB13-Pad52)") (class "Default")
      (node (ref "U103") (pin "52") (pinfunction "PB13_52") (pintype "bidirectional"))
    )
    (net (code "115") (name "unconnected-(U103A-PB14-Pad53)") (class "Default")
      (node (ref "U103") (pin "53") (pinfunction "PB14_53") (pintype "bidirectional"))
    )
    (net (code "116") (name "unconnected-(U103A-PB15-Pad54)") (class "Default")
      (node (ref "U103") (pin "54") (pinfunction "PB15_54") (pintype "bidirectional"))
    )
    (net (code "117") (name "unconnected-(U103A-PC2-Pad17)") (class "Default")
      (node (ref "U103") (pin "17") (pinfunction "PC2_17") (pintype "bidirectional"))
    )
    (net (code "118") (name "unconnected-(U103A-PC3-Pad18)") (class "Default")
      (node (ref "U103") (pin "18") (pinfunction "PC3_18") (pintype "bidirectional"))
    )
    (net (code "119") (name "unconnected-(U103A-PC4-Pad33)") (class "Default")
      (node (ref "U103") (pin "33") (pinfunction "PC4_33") (pintype "bidirectional"))
    )
    (net (code "120") (name "unconnected-(U103A-PC5-Pad34)") (class "Default")
      (node (ref "U103") (pin "34") (pinfunction "PC5_34") (pintype "bidirectional"))
    )
    (net (code "121") (name "unconnected-(U103A-PC9-Pad66)") (class "Default")
      (node (ref "U103") (pin "66") (pinfunction "PC9_66") (pintype "bidirectional"))
    )
    (net (code "122") (name "unconnected-(U103A-PC11-Pad79)") (class "Default")
      (node (ref "U103") (pin "79") (pinfunction "PC11_79") (pintype "bidirectional"))
    )
    (net (code "123") (name "unconnected-(U103A-PC12-Pad80)") (class "Default")
      (node (ref "U103") (pin "80") (pinfunction "PC12_80") (pintype "bidirectional"))
    )
    (net (code "124") (name "unconnected-(U103A-PC13-Pad7)") (class "Default")
      (node (ref "U103") (pin "7") (pinfunction "PC13_7") (pintype "bidirectional"))
    )
    (net (code "125") (name "unconnected-(U103A-PC14-OSC32_IN(PC14)-Pad8)") (class "Default")
      (node (ref "U103") (pin "8") (pinfunction "PC14-OSC32_IN(PC14)_8") (pintype "bidirectional"))
    )
    (net (code "126") (name "unconnected-(U103A-PC15-OSC32_OUT(PC15)-Pad9)") (class "Default")
      (node (ref "U103") (pin "9") (pinfunction "PC15-OSC32_OUT(PC15)_9") (pintype "bidirectional"))
    )
    (net (code "127") (name "unconnected-(U103A-PD1-Pad82)") (class "Default")
      (node (ref "U103") (pin "82") (pinfunction "PD1_82") (pintype "bidirectional"))
    )
    (net (code "128") (name "unconnected-(U103A-PD2-Pad83)") (class "Default")
      (node (ref "U103") (pin "83") (pinfunction "PD2_83") (pintype "bidirectional"))
    )
    (net (code "129") (name "unconnected-(U103A-PD3-Pad84)") (class "Default")
      (node (ref "U103") (pin "84") (pinfunction "PD3_84") (pintype "bidirectional"))
    )
    (net (code "130") (name "unconnected-(U103A-PD4-Pad85)") (class "Default")
      (node (ref "U103") (pin "85") (pinfunction "PD4_85") (pintype "bidirectional"))
    )
    (net (code "131") (name "unconnected-(U103A-PD5-Pad86)") (class "Default")
      (node (ref "U103") (pin "86") (pinfunction "PD5_86") (pintype "bidirectional"))
    )
    (net (code "132") (name "unconnected-(U103A-PD6-Pad87)") (class "Default")
      (node (ref "U103") (pin "87") (pinfunction "PD6_87") (pintype "bidirectional"))
    )
    (net (code "133") (name "unconnected-(U103A-PD7-Pad88)") (class "Default")
      (node (ref "U103") (pin "88") (pinfunction "PD7_88") (pintype "bidirectional"))
    )
    (net (code "134") (name "unconnected-(U103A-PD8-Pad55)") (class "Default")
      (node (ref "U103") (pin "55") (pinfunction "PD8_55") (pintype "bidirectional"))
    )
    (net (code "135") (name "unconnected-(U103A-PD9-Pad56)") (class "Default")
      (node (ref "U103") (pin "56") (pinfunction "PD9_56") (pintype "bidirectional"))
    )
    (net (code "136") (name "unconnected-(U103A-PD10-Pad57)") (class "Default")
      (node (ref "U103") (pin "57") (pinfunction "PD10_57") (pintype "bidirectional"))
    )
    (net (code "137") (name "unconnected-(U103A-PD11-Pad58)") (class "Default")
      (node (ref "U103") (pin "58") (pinfunction "PD11_58") (pintype "bidirectional"))
    )
    (net (code "138") (name "unconnected-(U103A-PD12-Pad59)") (class "Default")
      (node (ref "U103") (pin "59") (pinfunction "PD12_59") (pintype "bidirectional"))
    )
    (net (code "139") (name "unconnected-(U103A-PD13-Pad60)") (class "Default")
      (node (ref "U103") (pin "60") (pinfunction "PD13_60") (pintype "bidirectional"))
    )
    (net (code "140") (name "unconnected-(U103A-PD14-Pad61)") (class "Default")
      (node (ref "U103") (pin "61") (pinfunction "PD14_61") (pintype "bidirectional"))
    )
    (net (code "141") (name "unconnected-(U103A-PD15-Pad62)") (class "Default")
      (node (ref "U103") (pin "62") (pinfunction "PD15_62") (pintype "bidirectional"))
    )
    (net (code "142") (name "unconnected-(U103A-PE7-Pad38)") (class "Default")
      (node (ref "U103") (pin "38") (pinfunction "PE7_38") (pintype "bidirectional"))
    )
    (net (code "143") (name "unconnected-(U103A-PE8-Pad39)") (class "Default")
      (node (ref "U103") (pin "39") (pinfunction "PE8_39") (pintype "bidirectional"))
    )
    (net (code "144") (name "unconnected-(U103A-PE9-Pad40)") (class "Default")
      (node (ref "U103") (pin "40") (pinfunction "PE9_40") (pintype "bidirectional"))
    )
    (net (code "145") (name "unconnected-(U103A-PE10-Pad41)") (class "Default")
      (node (ref "U103") (pin "41") (pinfunction "PE10_41") (pintype "bidirectional"))
    )
    (net (code "146") (name "unconnected-(U103A-PE11-Pad42)") (class "Default")
      (node (ref "U103") (pin "42") (pinfunction "PE11_42") (pintype "bidirectional"))
    )
    (net (code "147") (name "unconnected-(U103A-PE12-Pad43)") (class "Default")
      (node (ref "U103") (pin "43") (pinfunction "PE12_43") (pintype "bidirectional"))
    )
    (net (code "148") (name "unconnected-(U103A-PE13-Pad44)") (class "Default")
      (node (ref "U103") (pin "44") (pinfunction "PE13_44") (pintype "bidirectional"))
    )
    (net (code "149") (name "unconnected-(U103A-PE14-Pad45)") (class "Default")
      (node (ref "U103") (pin "45") (pinfunction "PE14_45") (pintype "bidirectional"))
    )
    (net (code "150") (name "unconnected-(U103A-PE15-Pad46)") (class "Default")
      (node (ref "U103") (pin "46") (pinfunction "PE15_46") (pintype "bidirectional"))
    )
    (net (code "151") (name "unconnected-(U104-NC-Pad4)") (class "Default")
      (node (ref "U104") (pin "4") (pinfunction "NC_4") (pintype "passive+no_connect"))
    )
    (net (code "152") (name "unconnected-(U105-NC-Pad6)") (class "Default")
      (node (ref "U105") (pin "6") (pinfunction "NC_6") (pintype "passive+no_connect"))
    )
    (net (code "153") (name "unconnected-(U105-NC-Pad11)") (class "Default")
      (node (ref "U105") (pin "11") (pinfunction "NC_11") (pintype "passive+no_connect"))
    )
    (net (code "154") (name "unconnected-(U106-NC-Pad4)") (class "Default")
      (node (ref "U106") (pin "4") (pinfunction "NC_4") (pintype "passive+no_connect"))
    )
    (net (code "155") (name "unconnected-(U109-HYST-Pad2)") (class "Default")
      (node (ref "U109") (pin "2") (pinfunction "HYST_2") (pintype "passive+no_connect"))
    )
    (net (code "156") (name "unconnected-(U109-NC-Pad1)") (class "Default")
      (node (ref "U109") (pin "1") (pinfunction "NC_1") (pintype "passive+no_connect"))
    )
    (net (code "157") (name "unconnected-(U109-NC-Pad6)") (class "Default")
      (node (ref "U109") (pin "6") (pinfunction "NC_6") (pintype "passive+no_connect"))
    )
    (net (code "158") (name "unconnected-(U109-NC-Pad7)") (class "Default")
      (node (ref "U109") (pin "7") (pinfunction "NC_7") (pintype "passive+no_connect"))
    )
  )
)
